# bms_slave.net
KiCad netlist of a schematic drawn in Altium Designer
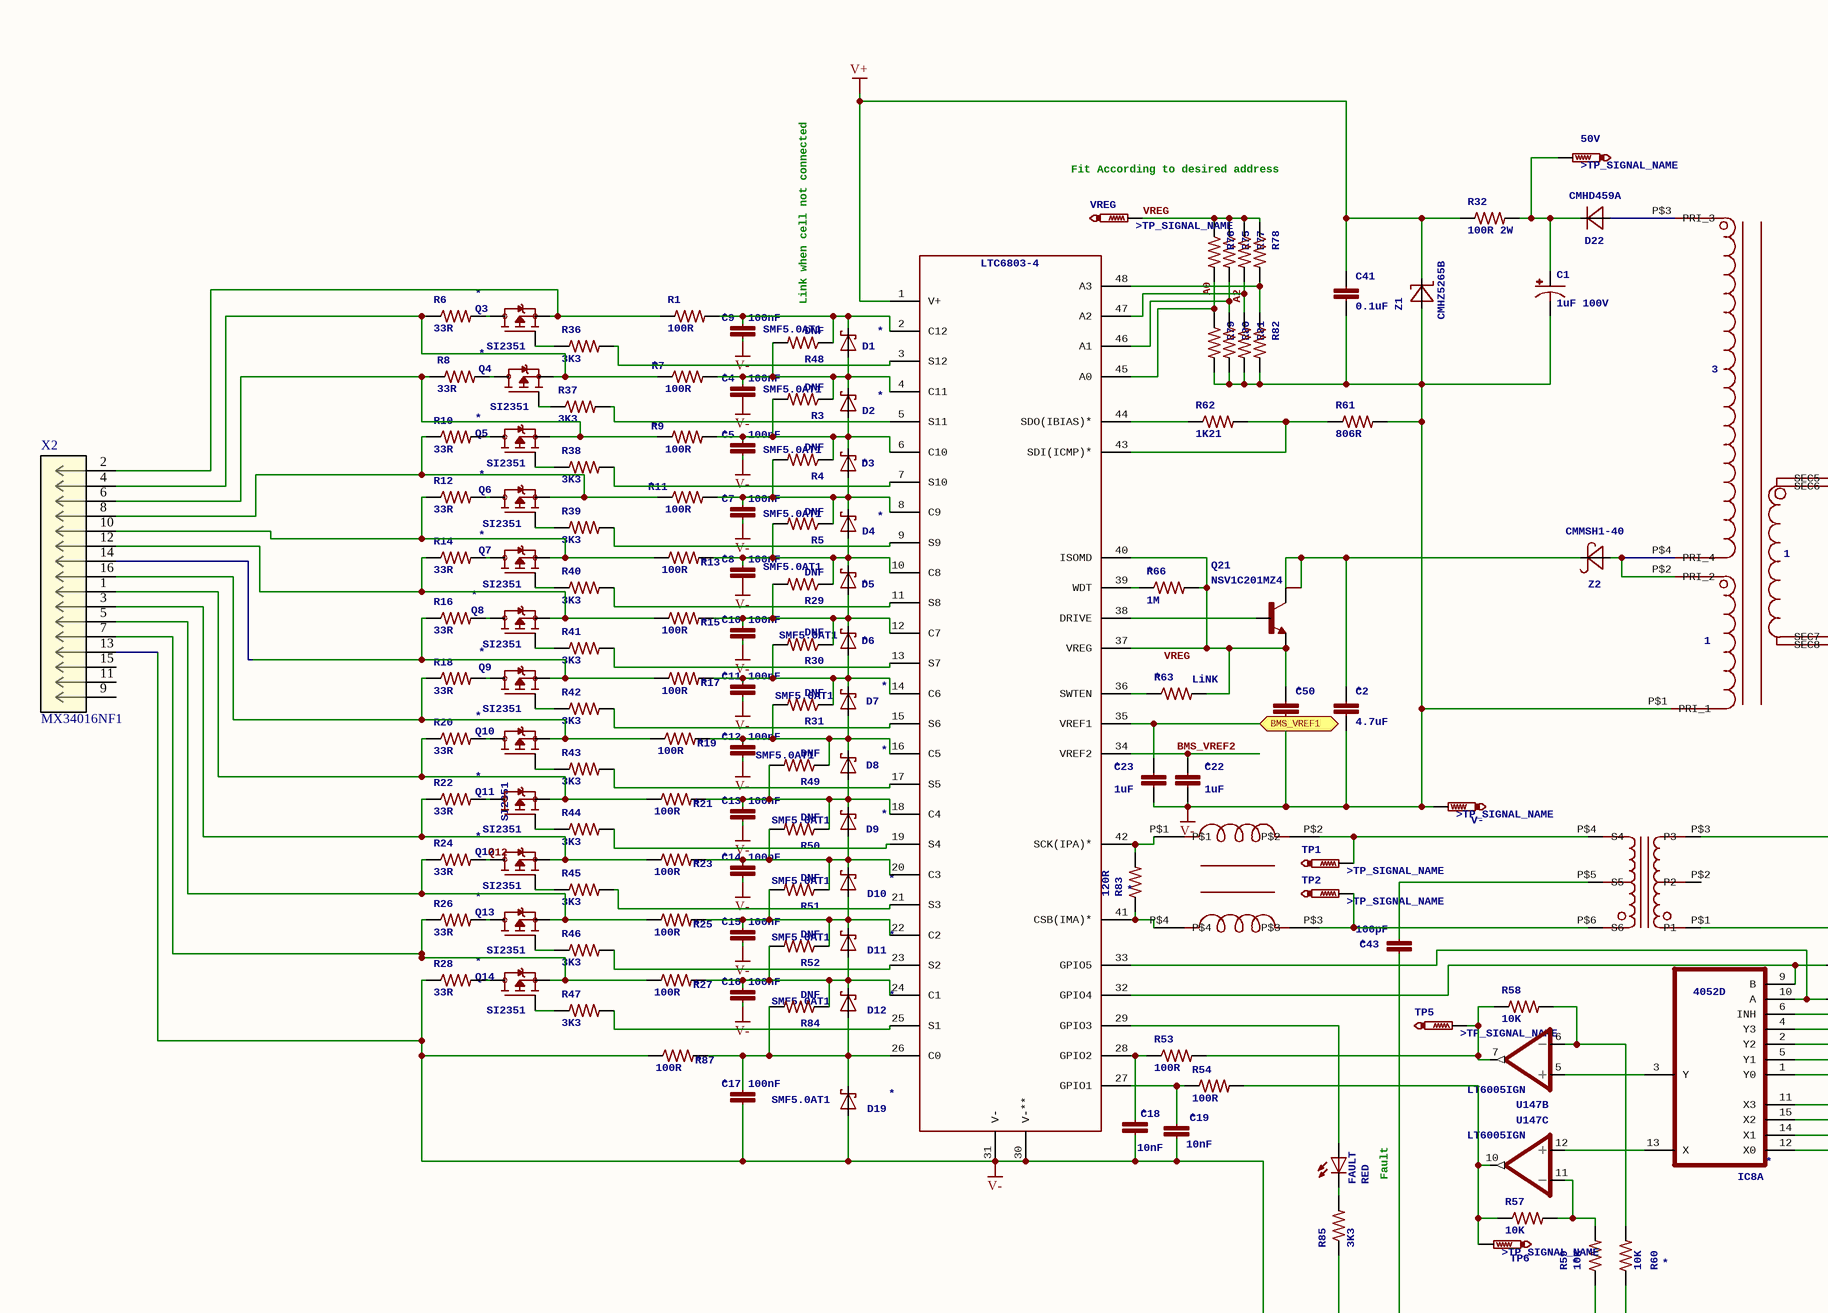
[diagram p0: bms_slave.SchDoc, top left]
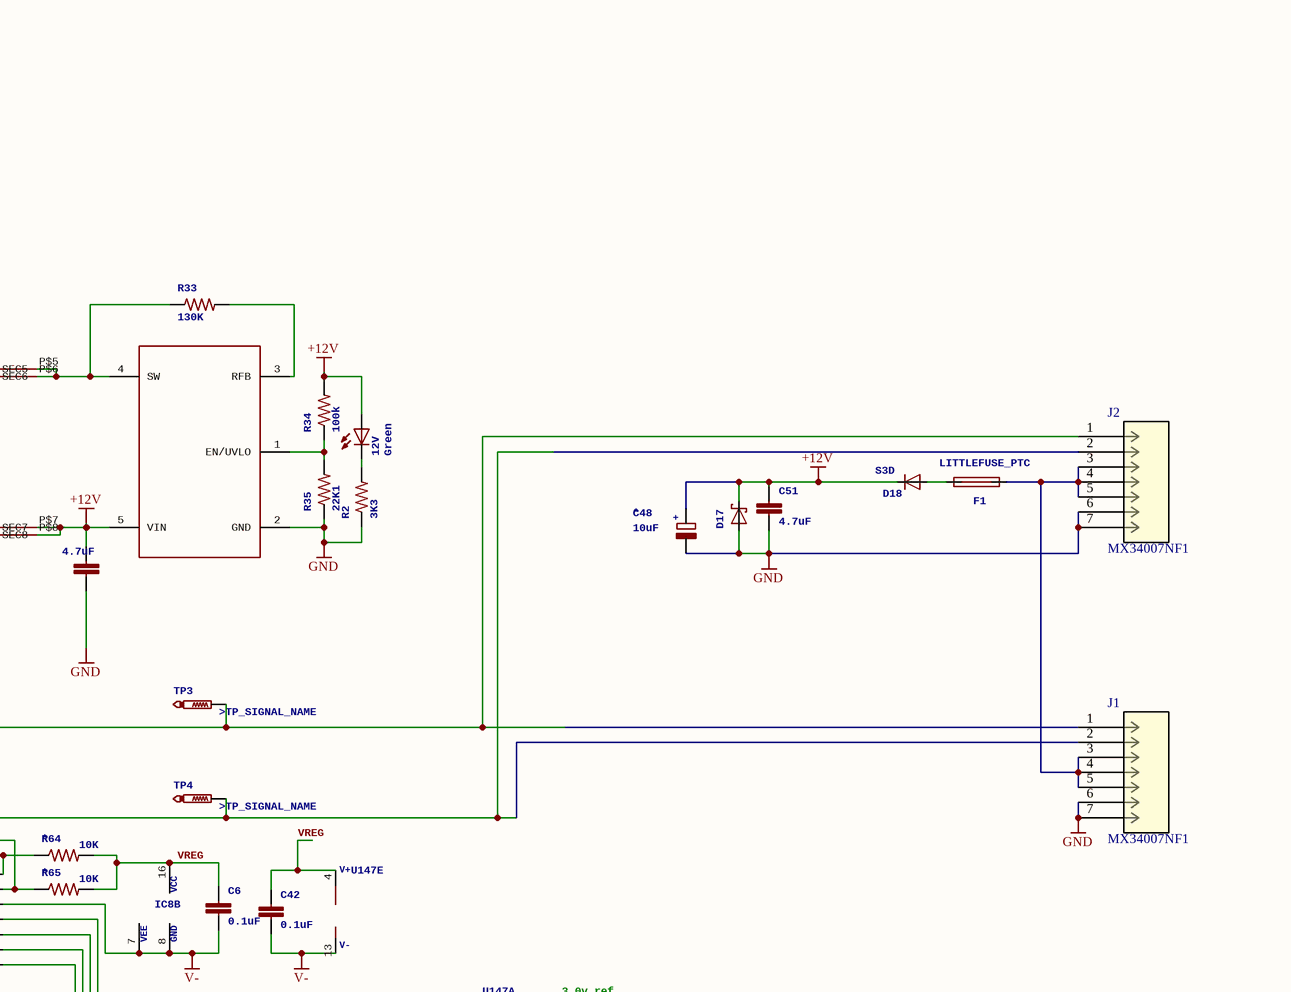
[diagram p1: bms_slave.SchDoc, top right]
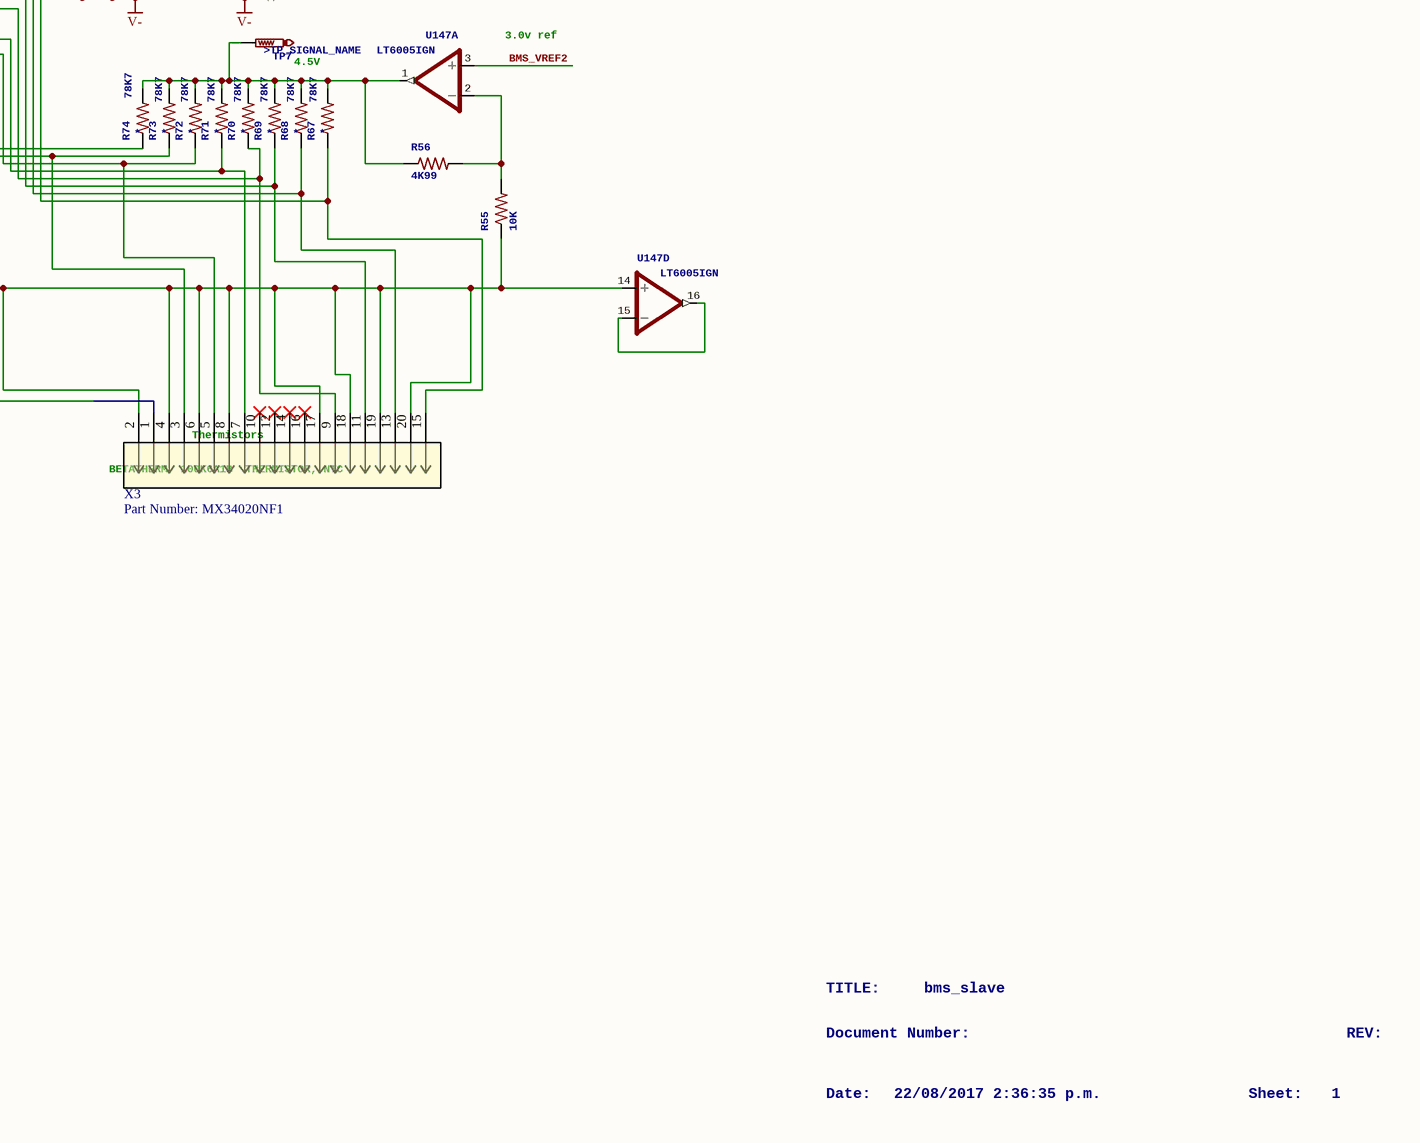
[diagram p2: bms_slave.SchDoc, bottom right]

(export (version "E")
  (design (tool "Eeschema 10.0.6"))
  (components
    (comp (ref "12V")
      (value "Green")
      (footprint "CHIP-LED0805")
      (libsource (lib "led") (part "LEDCHIP-LED0805"))
    )
    (comp (ref "50V")
      (value "PTR1PAD1-13")
      (footprint "P1-13")
      (description "TEST PIN")
      (fields (field (name "TP_SIGNAL_NAME") ">TP_SIGNAL_NAME"))
      (libsource (lib "testpad") (part "PTR1PAD1-13"))
    )
    (comp (ref "C1")
      (value "1uF 100V")
      (footprint "SMC_D")
      (description "POLARIZED CAPACITOR, American symbol")
      (libsource (lib "rcl") (part "CPOL-USSMCD"))
    )
    (comp (ref "C2")
      (value "4.7uF")
      (footprint "C1206")
      (description "CAPACITOR, European symbol")
      (fields (field (name "NAME") "*"))
      (libsource (lib "rcl") (part "C-EUC1206"))
    )
    (comp (ref "C3")
      (value "4.7uF")
      (footprint "C1206")
      (description "CAPACITOR, European symbol")
      (libsource (lib "rcl") (part "C-EUC1206"))
    )
    (comp (ref "C4")
      (value "100nF")
      (footprint "C0603@1")
      (fields (field (name "NAME") "*"))
      (libsource (lib "rcl") (part "C-EU-SMALL_0603"))
    )
    (comp (ref "C5")
      (value "100nF")
      (footprint "C0603@1")
      (fields (field (name "NAME") "*"))
      (libsource (lib "rcl") (part "C-EU-SMALL_0603"))
    )
    (comp (ref "C6")
      (value "0.1uF")
      (footprint "C1206")
      (description "CAPACITOR, European symbol")
      (libsource (lib "rcl") (part "C-EUC1206"))
    )
    (comp (ref "C7")
      (value "100nF")
      (footprint "C0603@1")
      (fields (field (name "NAME") "*"))
      (libsource (lib "rcl") (part "C-EU-SMALL_0603"))
    )
    (comp (ref "C8")
      (value "100nF")
      (footprint "C0603@1")
      (fields (field (name "NAME") "*"))
      (libsource (lib "rcl") (part "C-EU-SMALL_0603"))
    )
    (comp (ref "C9")
      (value "100nF")
      (footprint "C0603@1")
      (fields (field (name "NAME") "*"))
      (libsource (lib "rcl") (part "C-EU-SMALL_0603"))
    )
    (comp (ref "C10")
      (value "100nF")
      (footprint "C0603@1")
      (fields (field (name "NAME") "*"))
      (libsource (lib "rcl") (part "C-EU-SMALL_0603"))
    )
    (comp (ref "C11")
      (value "100nF")
      (footprint "C0603@1")
      (fields (field (name "NAME") "*"))
      (libsource (lib "rcl") (part "C-EU-SMALL_0603"))
    )
    (comp (ref "C12")
      (value "100nF")
      (footprint "C0603@1")
      (fields (field (name "NAME") "*"))
      (libsource (lib "rcl") (part "C-EU-SMALL_0603"))
    )
    (comp (ref "C13")
      (value "100nF")
      (footprint "C0603@1")
      (fields (field (name "NAME") "*"))
      (libsource (lib "rcl") (part "C-EU-SMALL_0603"))
    )
    (comp (ref "C14")
      (value "100nF")
      (footprint "C0603@1")
      (fields (field (name "NAME") "*"))
      (libsource (lib "rcl") (part "C-EU-SMALL_0603"))
    )
    (comp (ref "C15")
      (value "100nF")
      (footprint "C0603@1")
      (fields (field (name "NAME") "*"))
      (libsource (lib "rcl") (part "C-EU-SMALL_0603"))
    )
    (comp (ref "C16")
      (value "100nF")
      (footprint "C0603@1")
      (fields (field (name "NAME") "*"))
      (libsource (lib "rcl") (part "C-EU-SMALL_0603"))
    )
    (comp (ref "C17")
      (value "100nF")
      (footprint "C0603@1")
      (fields (field (name "NAME") "*"))
      (libsource (lib "rcl") (part "C-EU-SMALL_0603"))
    )
    (comp (ref "C18")
      (value "10nF")
      (footprint "C0603@1")
      (fields (field (name "NAME") "*"))
      (libsource (lib "rcl") (part "C-EU-SMALL_0603"))
    )
    (comp (ref "C19")
      (value "10nF")
      (footprint "C0603@1")
      (fields (field (name "NAME") "*"))
      (libsource (lib "rcl") (part "C-EU-SMALL_0603"))
    )
    (comp (ref "C22")
      (value "1uF")
      (footprint "C1206")
      (description "CAPACITOR, European symbol")
      (fields (field (name "NAME") "*"))
      (libsource (lib "rcl") (part "C-EUC1206"))
    )
    (comp (ref "C23")
      (value "1uF")
      (footprint "C1206")
      (description "CAPACITOR, European symbol")
      (fields (field (name "NAME") "*"))
      (libsource (lib "rcl") (part "C-EUC1206"))
    )
    (comp (ref "C41")
      (value "0.1uF")
      (footprint "C1206")
      (description "CAPACITOR, European symbol")
      (libsource (lib "rcl") (part "C-EUC1206"))
    )
    (comp (ref "C42")
      (value "0.1uF")
      (footprint "C1206")
      (description "CAPACITOR, European symbol")
      (libsource (lib "rcl") (part "C-EUC1206"))
    )
    (comp (ref "C43")
      (value "100pF")
      (footprint "C1206@1")
      (fields (field (name "NAME") "*"))
      (libsource (lib "rcl") (part "C-EU-SMALL"))
    )
    (comp (ref "C48")
      (value "10uF")
      (footprint "SMC_D")
      (description "POLARIZED CAPACITOR, European symbol")
      (fields (field (name "NAME") "*") (field (name "+") "+"))
      (libsource (lib "rcl") (part "CPOL-EUSMCD"))
    )
    (comp (ref "C50")
      (value "1uF")
      (footprint "C1206")
      (description "CAPACITOR, European symbol")
      (fields (field (name "NAME") "*"))
      (libsource (lib "rcl") (part "C-EUC1206"))
    )
    (comp (ref "C51")
      (value "4.7uF")
      (footprint "C1206")
      (description "CAPACITOR, European symbol")
      (libsource (lib "rcl") (part "C-EUC1206"))
    )
    (comp (ref "D1")
      (value "SMF5.0AT1")
      (footprint "SOD123FL")
      (description "200 W Transient Voltage Suppressor   Source: Data sheet")
      (fields (field (name "NAME") "*"))
      (libsource (lib "diode") (part "SMF5.0AT1"))
    )
    (comp (ref "D2")
      (value "SMF5.0AT1")
      (footprint "SOD123FL")
      (description "200 W Transient Voltage Suppressor   Source: Data sheet")
      (fields (field (name "NAME") "*"))
      (libsource (lib "diode") (part "SMF5.0AT1"))
    )
    (comp (ref "D3")
      (value "SMF5.0AT1")
      (footprint "SOD123FL")
      (description "200 W Transient Voltage Suppressor   Source: Data sheet")
      (fields (field (name "NAME") "*"))
      (libsource (lib "diode") (part "SMF5.0AT1"))
    )
    (comp (ref "D4")
      (value "SMF5.0AT1")
      (footprint "SOD123FL")
      (description "200 W Transient Voltage Suppressor   Source: Data sheet")
      (fields (field (name "NAME") "*"))
      (libsource (lib "diode") (part "SMF5.0AT1"))
    )
    (comp (ref "D5")
      (value "SMF5.0AT1")
      (footprint "SOD123FL")
      (description "200 W Transient Voltage Suppressor   Source: Data sheet")
      (fields (field (name "NAME") "*"))
      (libsource (lib "diode") (part "SMF5.0AT1"))
    )
    (comp (ref "D6")
      (value "SMF5.0AT1")
      (footprint "SOD123FL")
      (description "200 W Transient Voltage Suppressor   Source: Data sheet")
      (fields (field (name "NAME") "*"))
      (libsource (lib "diode") (part "SMF5.0AT1"))
    )
    (comp (ref "D7")
      (value "SMF5.0AT1")
      (footprint "SOD123FL")
      (description "200 W Transient Voltage Suppressor   Source: Data sheet")
      (fields (field (name "NAME") "*"))
      (libsource (lib "diode") (part "SMF5.0AT1"))
    )
    (comp (ref "D8")
      (value "SMF5.0AT1")
      (footprint "SOD123FL")
      (description "200 W Transient Voltage Suppressor   Source: Data sheet")
      (fields (field (name "NAME") "*"))
      (libsource (lib "diode") (part "SMF5.0AT1"))
    )
    (comp (ref "D9")
      (value "SMF5.0AT1")
      (footprint "SOD123FL")
      (description "200 W Transient Voltage Suppressor   Source: Data sheet")
      (fields (field (name "NAME") "*"))
      (libsource (lib "diode") (part "SMF5.0AT1"))
    )
    (comp (ref "D10")
      (value "SMF5.0AT1")
      (footprint "SOD123FL")
      (description "200 W Transient Voltage Suppressor   Source: Data sheet")
      (fields (field (name "NAME") "*"))
      (libsource (lib "diode") (part "SMF5.0AT1"))
    )
    (comp (ref "D11")
      (value "SMF5.0AT1")
      (footprint "SOD123FL")
      (description "200 W Transient Voltage Suppressor   Source: Data sheet")
      (fields (field (name "NAME") "*"))
      (libsource (lib "diode") (part "SMF5.0AT1"))
    )
    (comp (ref "D12")
      (value "SMF5.0AT1")
      (footprint "SOD123FL")
      (description "200 W Transient Voltage Suppressor   Source: Data sheet")
      (fields (field (name "NAME") "*"))
      (libsource (lib "diode") (part "SMF5.0AT1"))
    )
    (comp (ref "D17")
      (value "SCHOTTKY-DIODESMC")
      (footprint "SMC")
      (description "Schottky Diode")
      (libsource (lib "diode") (part "SCHOTTKY-DIODESMC"))
    )
    (comp (ref "D18")
      (value "S3D")
      (footprint "SMC")
      (description "DIODE")
      (libsource (lib "diode") (part "DIODE-SMC"))
    )
    (comp (ref "D19")
      (value "SMF5.0AT1")
      (footprint "SOD123FL")
      (description "200 W Transient Voltage Suppressor   Source: Data sheet")
      (fields (field (name "NAME") "*"))
      (libsource (lib "diode") (part "SMF5.0AT1"))
    )
    (comp (ref "D22") (value "CMHD459A") (footprint "SOD123") (libsource (lib "diode") (part "CMHD459A")))
    (comp (ref "F1")
      (value "LITTLEFUSE_PTC")
      (footprint "1812")
      (libsource (lib "fuse") (part "LITTLEFUSE_PTC"))
    )
    (comp (ref "FAULT")
      (value "RED")
      (footprint "CHIP-LED0805")
      (libsource (lib "led") (part "LEDCHIP-LED0805"))
    )
    (comp (ref "IC8")
      (value "4052D")
      (footprint "SO16")
      (description "Dual 4-channel ANALOG MULTIPLEXER")
      (fields
        (field (name "NAME") "*")
        (field (name "VEE") "VEE")
        (field (name "GND") "GND")
        (field (name "VCC") "VCC")
      )
      (libsource (lib "40xx") (part "4052D"))
    )
    (comp (ref "J1")
      (value "MX34007NF1")
      (footprint "CONN_MX34007NF1")
      (libsource (lib "2020-03-25_00-51-49") (part "MX34007NF1"))
    )
    (comp (ref "J2")
      (value "MX34007NF1")
      (footprint "CONN_MX34007NF1")
      (libsource (lib "2020-03-25_00-51-49") (part "MX34007NF1"))
    )
    (comp (ref "Q3")
      (value "SI2351")
      (footprint "SOT23")
      (fields (field (name "NAME") "*"))
      (libsource (lib "transistor-fet") (part "SI2351"))
    )
    (comp (ref "Q4")
      (value "SI2351")
      (footprint "SOT23")
      (fields (field (name "NAME") "*"))
      (libsource (lib "transistor-fet") (part "SI2351"))
    )
    (comp (ref "Q5")
      (value "SI2351")
      (footprint "SOT23")
      (fields (field (name "NAME") "*"))
      (libsource (lib "transistor-fet") (part "SI2351"))
    )
    (comp (ref "Q6")
      (value "SI2351")
      (footprint "SOT23")
      (fields (field (name "NAME") "*"))
      (libsource (lib "transistor-fet") (part "SI2351"))
    )
    (comp (ref "Q7")
      (value "SI2351")
      (footprint "SOT23")
      (fields (field (name "NAME") "*"))
      (libsource (lib "transistor-fet") (part "SI2351"))
    )
    (comp (ref "Q8")
      (value "SI2351")
      (footprint "SOT23")
      (fields (field (name "NAME") "*"))
      (libsource (lib "transistor-fet") (part "SI2351"))
    )
    (comp (ref "Q9")
      (value "SI2351")
      (footprint "SOT23")
      (fields (field (name "NAME") "*"))
      (libsource (lib "transistor-fet") (part "SI2351"))
    )
    (comp (ref "Q10")
      (value "SI2351")
      (footprint "SOT23")
      (fields (field (name "NAME") "*"))
      (libsource (lib "transistor-fet") (part "SI2351"))
    )
    (comp (ref "Q11")
      (value "SI2351")
      (footprint "SOT23")
      (fields (field (name "NAME") "*"))
      (libsource (lib "transistor-fet") (part "SI2351"))
    )
    (comp (ref "Q12")
      (value "SI2351")
      (footprint "SOT23")
      (fields (field (name "NAME") "*"))
      (libsource (lib "transistor-fet") (part "SI2351"))
    )
    (comp (ref "Q13")
      (value "SI2351")
      (footprint "SOT23")
      (fields (field (name "NAME") "*"))
      (libsource (lib "transistor-fet") (part "SI2351"))
    )
    (comp (ref "Q14")
      (value "SI2351")
      (footprint "SOT23")
      (fields (field (name "NAME") "*"))
      (libsource (lib "transistor-fet") (part "SI2351"))
    )
    (comp (ref "Q21")
      (value "NSV1C201MZ4")
      (footprint "SOT223")
      (libsource (lib "transistor-npn") (part "NSV1C201MZ4"))
    )
    (comp (ref "R1")
      (value "100R")
      (footprint "R0603")
      (description "RESISTOR, American symbol")
      (libsource (lib "rcl") (part "R-US_R0603"))
    )
    (comp (ref "R2")
      (value "3K3")
      (footprint "R0603")
      (description "RESISTOR, American symbol")
      (libsource (lib "rcl") (part "R-US_R0603"))
    )
    (comp (ref "R3")
      (value "DNF")
      (footprint "R0603")
      (description "RESISTOR, American symbol")
      (libsource (lib "rcl") (part "R-US_R0603"))
    )
    (comp (ref "R4")
      (value "DNF")
      (footprint "R0603")
      (description "RESISTOR, American symbol")
      (libsource (lib "rcl") (part "R-US_R0603"))
    )
    (comp (ref "R5")
      (value "DNF")
      (footprint "R0603")
      (description "RESISTOR, American symbol")
      (libsource (lib "rcl") (part "R-US_R0603"))
    )
    (comp (ref "R6")
      (value "33R")
      (footprint "R2512")
      (description "RESISTOR, American symbol")
      (libsource (lib "rcl") (part "R-US_R2512"))
    )
    (comp (ref "R7")
      (value "100R")
      (footprint "R0603")
      (description "RESISTOR, American symbol")
      (fields (field (name "NAME") "*"))
      (libsource (lib "rcl") (part "R-US_R0603"))
    )
    (comp (ref "R8")
      (value "33R")
      (footprint "R2512")
      (description "RESISTOR, American symbol")
      (libsource (lib "rcl") (part "R-US_R2512"))
    )
    (comp (ref "R9")
      (value "100R")
      (footprint "R0603")
      (description "RESISTOR, American symbol")
      (fields (field (name "NAME") "*"))
      (libsource (lib "rcl") (part "R-US_R0603"))
    )
    (comp (ref "R10")
      (value "33R")
      (footprint "R2512")
      (description "RESISTOR, American symbol")
      (libsource (lib "rcl") (part "R-US_R2512"))
    )
    (comp (ref "R11")
      (value "100R")
      (footprint "R0603")
      (description "RESISTOR, American symbol")
      (fields (field (name "NAME") "*"))
      (libsource (lib "rcl") (part "R-US_R0603"))
    )
    (comp (ref "R12")
      (value "33R")
      (footprint "R2512")
      (description "RESISTOR, American symbol")
      (libsource (lib "rcl") (part "R-US_R2512"))
    )
    (comp (ref "R13")
      (value "100R")
      (footprint "R0603")
      (description "RESISTOR, American symbol")
      (fields (field (name "NAME") "*"))
      (libsource (lib "rcl") (part "R-US_R0603"))
    )
    (comp (ref "R14")
      (value "33R")
      (footprint "R2512")
      (description "RESISTOR, American symbol")
      (libsource (lib "rcl") (part "R-US_R2512"))
    )
    (comp (ref "R15")
      (value "100R")
      (footprint "R0603")
      (description "RESISTOR, American symbol")
      (fields (field (name "NAME") "*"))
      (libsource (lib "rcl") (part "R-US_R0603"))
    )
    (comp (ref "R16")
      (value "33R")
      (footprint "R2512")
      (description "RESISTOR, American symbol")
      (libsource (lib "rcl") (part "R-US_R2512"))
    )
    (comp (ref "R17")
      (value "100R")
      (footprint "R0603")
      (description "RESISTOR, American symbol")
      (fields (field (name "NAME") "*"))
      (libsource (lib "rcl") (part "R-US_R0603"))
    )
    (comp (ref "R18")
      (value "33R")
      (footprint "R2512")
      (description "RESISTOR, American symbol")
      (libsource (lib "rcl") (part "R-US_R2512"))
    )
    (comp (ref "R19")
      (value "100R")
      (footprint "R0603")
      (description "RESISTOR, American symbol")
      (fields (field (name "NAME") "*"))
      (libsource (lib "rcl") (part "R-US_R0603"))
    )
    (comp (ref "R20")
      (value "33R")
      (footprint "R2512")
      (description "RESISTOR, American symbol")
      (libsource (lib "rcl") (part "R-US_R2512"))
    )
    (comp (ref "R21")
      (value "100R")
      (footprint "R0603")
      (description "RESISTOR, American symbol")
      (fields (field (name "NAME") "*"))
      (libsource (lib "rcl") (part "R-US_R0603"))
    )
    (comp (ref "R22")
      (value "33R")
      (footprint "R2512")
      (description "RESISTOR, American symbol")
      (libsource (lib "rcl") (part "R-US_R2512"))
    )
    (comp (ref "R23")
      (value "100R")
      (footprint "R0603")
      (description "RESISTOR, American symbol")
      (fields (field (name "NAME") "*"))
      (libsource (lib "rcl") (part "R-US_R0603"))
    )
    (comp (ref "R24")
      (value "33R")
      (footprint "R2512")
      (description "RESISTOR, American symbol")
      (libsource (lib "rcl") (part "R-US_R2512"))
    )
    (comp (ref "R25")
      (value "100R")
      (footprint "R0603")
      (description "RESISTOR, American symbol")
      (fields (field (name "NAME") "*"))
      (libsource (lib "rcl") (part "R-US_R0603"))
    )
    (comp (ref "R26")
      (value "33R")
      (footprint "R2512")
      (description "RESISTOR, American symbol")
      (libsource (lib "rcl") (part "R-US_R2512"))
    )
    (comp (ref "R27")
      (value "100R")
      (footprint "R0603")
      (description "RESISTOR, American symbol")
      (fields (field (name "NAME") "*"))
      (libsource (lib "rcl") (part "R-US_R0603"))
    )
    (comp (ref "R28")
      (value "33R")
      (footprint "R2512")
      (description "RESISTOR, American symbol")
      (libsource (lib "rcl") (part "R-US_R2512"))
    )
    (comp (ref "R29")
      (value "DNF")
      (footprint "R0603")
      (description "RESISTOR, American symbol")
      (libsource (lib "rcl") (part "R-US_R0603"))
    )
    (comp (ref "R30")
      (value "DNF")
      (footprint "R0603")
      (description "RESISTOR, American symbol")
      (libsource (lib "rcl") (part "R-US_R0603"))
    )
    (comp (ref "R31")
      (value "DNF")
      (footprint "R0603")
      (description "RESISTOR, American symbol")
      (libsource (lib "rcl") (part "R-US_R0603"))
    )
    (comp (ref "R32")
      (value "100R 2W")
      (footprint "R2512")
      (description "RESISTOR, American symbol")
      (libsource (lib "rcl") (part "R-US_R2512"))
    )
    (comp (ref "R33")
      (value "130K")
      (footprint "R0603")
      (description "RESISTOR, American symbol")
      (libsource (lib "rcl") (part "R-US_R0603"))
    )
    (comp (ref "R34")
      (value "100k")
      (footprint "R0603")
      (description "RESISTOR, American symbol")
      (libsource (lib "rcl") (part "R-US_R0603"))
    )
    (comp (ref "R35")
      (value "22K1")
      (footprint "R0603")
      (description "RESISTOR, American symbol")
      (libsource (lib "rcl") (part "R-US_R0603"))
    )
    (comp (ref "R36")
      (value "3K3")
      (footprint "R0603")
      (description "RESISTOR, American symbol")
      (libsource (lib "rcl") (part "R-US_R0603"))
    )
    (comp (ref "R37")
      (value "3K3")
      (footprint "R0603")
      (description "RESISTOR, American symbol")
      (libsource (lib "rcl") (part "R-US_R0603"))
    )
    (comp (ref "R38")
      (value "3K3")
      (footprint "R0603")
      (description "RESISTOR, American symbol")
      (libsource (lib "rcl") (part "R-US_R0603"))
    )
    (comp (ref "R39")
      (value "3K3")
      (footprint "R0603")
      (description "RESISTOR, American symbol")
      (libsource (lib "rcl") (part "R-US_R0603"))
    )
    (comp (ref "R40")
      (value "3K3")
      (footprint "R0603")
      (description "RESISTOR, American symbol")
      (libsource (lib "rcl") (part "R-US_R0603"))
    )
    (comp (ref "R41")
      (value "3K3")
      (footprint "R0603")
      (description "RESISTOR, American symbol")
      (libsource (lib "rcl") (part "R-US_R0603"))
    )
    (comp (ref "R42")
      (value "3K3")
      (footprint "R0603")
      (description "RESISTOR, American symbol")
      (libsource (lib "rcl") (part "R-US_R0603"))
    )
    (comp (ref "R43")
      (value "3K3")
      (footprint "R0603")
      (description "RESISTOR, American symbol")
      (libsource (lib "rcl") (part "R-US_R0603"))
    )
    (comp (ref "R44")
      (value "3K3")
      (footprint "R0603")
      (description "RESISTOR, American symbol")
      (libsource (lib "rcl") (part "R-US_R0603"))
    )
    (comp (ref "R45")
      (value "3K3")
      (footprint "R0603")
      (description "RESISTOR, American symbol")
      (libsource (lib "rcl") (part "R-US_R0603"))
    )
    (comp (ref "R46")
      (value "3K3")
      (footprint "R0603")
      (description "RESISTOR, American symbol")
      (libsource (lib "rcl") (part "R-US_R0603"))
    )
    (comp (ref "R47")
      (value "3K3")
      (footprint "R0603")
      (description "RESISTOR, American symbol")
      (libsource (lib "rcl") (part "R-US_R0603"))
    )
    (comp (ref "R48")
      (value "DNF")
      (footprint "R0603")
      (description "RESISTOR, American symbol")
      (libsource (lib "rcl") (part "R-US_R0603"))
    )
    (comp (ref "R49")
      (value "DNF")
      (footprint "R0603")
      (description "RESISTOR, American symbol")
      (libsource (lib "rcl") (part "R-US_R0603"))
    )
    (comp (ref "R50")
      (value "DNF")
      (footprint "R0603")
      (description "RESISTOR, American symbol")
      (libsource (lib "rcl") (part "R-US_R0603"))
    )
    (comp (ref "R51")
      (value "DNF")
      (footprint "R0603")
      (description "RESISTOR, American symbol")
      (libsource (lib "rcl") (part "R-US_R0603"))
    )
    (comp (ref "R52")
      (value "DNF")
      (footprint "R0603")
      (description "RESISTOR, American symbol")
      (libsource (lib "rcl") (part "R-US_R0603"))
    )
    (comp (ref "R53")
      (value "100R")
      (footprint "R0603")
      (description "RESISTOR, American symbol")
      (libsource (lib "rcl") (part "R-US_R0603"))
    )
    (comp (ref "R54")
      (value "100R")
      (footprint "R0603")
      (description "RESISTOR, American symbol")
      (libsource (lib "rcl") (part "R-US_R0603"))
    )
    (comp (ref "R55")
      (value "10K")
      (footprint "R0603")
      (description "RESISTOR, American symbol")
      (libsource (lib "rcl") (part "R-US_R0603"))
    )
    (comp (ref "R56")
      (value "4K99")
      (footprint "R0603")
      (description "RESISTOR, American symbol")
      (libsource (lib "rcl") (part "R-US_R0603"))
    )
    (comp (ref "R57")
      (value "10K")
      (footprint "R0603")
      (description "RESISTOR, American symbol")
      (libsource (lib "rcl") (part "R-US_R0603"))
    )
    (comp (ref "R58")
      (value "10K")
      (footprint "R0603")
      (description "RESISTOR, American symbol")
      (libsource (lib "rcl") (part "R-US_R0603"))
    )
    (comp (ref "R59")
      (value "10K")
      (footprint "R0603")
      (description "RESISTOR, American symbol")
      (fields (field (name "NAME") "*"))
      (libsource (lib "rcl") (part "R-US_R0603"))
    )
    (comp (ref "R60")
      (value "10K")
      (footprint "R0603")
      (description "RESISTOR, American symbol")
      (fields (field (name "NAME") "*"))
      (libsource (lib "rcl") (part "R-US_R0603"))
    )
    (comp (ref "R61")
      (value "806R")
      (footprint "R0603")
      (description "RESISTOR, American symbol")
      (libsource (lib "rcl") (part "R-US_R0603"))
    )
    (comp (ref "R62")
      (value "1K21")
      (footprint "R0603")
      (description "RESISTOR, American symbol")
      (libsource (lib "rcl") (part "R-US_R0603"))
    )
    (comp (ref "R63")
      (value "LiNK")
      (footprint "R0603")
      (description "RESISTOR, American symbol")
      (fields (field (name "NAME") "*"))
      (libsource (lib "rcl") (part "R-US_R0603"))
    )
    (comp (ref "R64")
      (value "10K")
      (footprint "R0603")
      (description "RESISTOR, American symbol")
      (fields (field (name "NAME") "*"))
      (libsource (lib "rcl") (part "R-US_R0603"))
    )
    (comp (ref "R65")
      (value "10K")
      (footprint "R0603")
      (description "RESISTOR, American symbol")
      (fields (field (name "NAME") "*"))
      (libsource (lib "rcl") (part "R-US_R0603"))
    )
    (comp (ref "R66")
      (value "1M")
      (footprint "R0603")
      (description "RESISTOR, American symbol")
      (fields (field (name "NAME") "*"))
      (libsource (lib "rcl") (part "R-US_R0603"))
    )
    (comp (ref "R67")
      (value "78K7")
      (footprint "R0603")
      (description "RESISTOR, American symbol")
      (fields (field (name "NAME") "*"))
      (libsource (lib "rcl") (part "R-US_R0603"))
    )
    (comp (ref "R68")
      (value "78K7")
      (footprint "R0603")
      (description "RESISTOR, American symbol")
      (fields (field (name "NAME") "*"))
      (libsource (lib "rcl") (part "R-US_R0603"))
    )
    (comp (ref "R69")
      (value "78K7")
      (footprint "R0603")
      (description "RESISTOR, American symbol")
      (fields (field (name "NAME") "*"))
      (libsource (lib "rcl") (part "R-US_R0603"))
    )
    (comp (ref "R70")
      (value "78K7")
      (footprint "R0603")
      (description "RESISTOR, American symbol")
      (fields (field (name "NAME") "*"))
      (libsource (lib "rcl") (part "R-US_R0603"))
    )
    (comp (ref "R71")
      (value "78K7")
      (footprint "R0603")
      (description "RESISTOR, American symbol")
      (fields (field (name "NAME") "*"))
      (libsource (lib "rcl") (part "R-US_R0603"))
    )
    (comp (ref "R72")
      (value "78K7")
      (footprint "R0603")
      (description "RESISTOR, American symbol")
      (fields (field (name "NAME") "*"))
      (libsource (lib "rcl") (part "R-US_R0603"))
    )
    (comp (ref "R73")
      (value "78K7")
      (footprint "R0603")
      (description "RESISTOR, American symbol")
      (fields (field (name "NAME") "*"))
      (libsource (lib "rcl") (part "R-US_R0603"))
    )
    (comp (ref "R74")
      (value "78K7")
      (footprint "R0603")
      (description "RESISTOR, American symbol")
      (fields (field (name "NAME") "*"))
      (libsource (lib "rcl") (part "R-US_R0603"))
    )
    (comp (ref "R75")
      (value "R-US_R0603")
      (footprint "R0603")
      (description "RESISTOR, American symbol")
      (libsource (lib "rcl") (part "R-US_R0603"))
    )
    (comp (ref "R76")
      (value "R-US_R0603")
      (footprint "R0603")
      (description "RESISTOR, American symbol")
      (libsource (lib "rcl") (part "R-US_R0603"))
    )
    (comp (ref "R77")
      (value "R-US_R0603")
      (footprint "R0603")
      (description "RESISTOR, American symbol")
      (libsource (lib "rcl") (part "R-US_R0603"))
    )
    (comp (ref "R78")
      (value "R-US_R0603")
      (footprint "R0603")
      (description "RESISTOR, American symbol")
      (libsource (lib "rcl") (part "R-US_R0603"))
    )
    (comp (ref "R79")
      (value "R-US_R0603")
      (footprint "R0603")
      (description "RESISTOR, American symbol")
      (libsource (lib "rcl") (part "R-US_R0603"))
    )
    (comp (ref "R80")
      (value "R-US_R0603")
      (footprint "R0603")
      (description "RESISTOR, American symbol")
      (libsource (lib "rcl") (part "R-US_R0603"))
    )
    (comp (ref "R81")
      (value "R-US_R0603")
      (footprint "R0603")
      (description "RESISTOR, American symbol")
      (libsource (lib "rcl") (part "R-US_R0603"))
    )
    (comp (ref "R82")
      (value "R-US_R0603")
      (footprint "R0603")
      (description "RESISTOR, American symbol")
      (libsource (lib "rcl") (part "R-US_R0603"))
    )
    (comp (ref "R83")
      (value "120R")
      (footprint "R0603")
      (description "RESISTOR, American symbol")
      (fields (field (name "NAME") "*"))
      (libsource (lib "rcl") (part "R-US_R0603"))
    )
    (comp (ref "R84")
      (value "DNF")
      (footprint "R0603")
      (description "RESISTOR, American symbol")
      (libsource (lib "rcl") (part "R-US_R0603"))
    )
    (comp (ref "R85")
      (value "3K3")
      (footprint "R0603")
      (description "RESISTOR, American symbol")
      (libsource (lib "rcl") (part "R-US_R0603"))
    )
    (comp (ref "R87")
      (value "100R")
      (footprint "R0603")
      (description "RESISTOR, American symbol")
      (fields (field (name "NAME") "*"))
      (libsource (lib "rcl") (part "R-US_R0603"))
    )
    (comp (ref "TP1")
      (value "PTR1PAD1-13")
      (footprint "P1-13")
      (description "TEST PIN")
      (fields (field (name "TP_SIGNAL_NAME") ">TP_SIGNAL_NAME"))
      (libsource (lib "") (part "PTR1PAD1-13_1"))
    )
    (comp (ref "TP2")
      (value "PTR1PAD1-13")
      (footprint "P1-13")
      (description "TEST PIN")
      (fields (field (name "TP_SIGNAL_NAME") ">TP_SIGNAL_NAME"))
      (libsource (lib "") (part "PTR1PAD1-13_1"))
    )
    (comp (ref "TP3")
      (value "PTR1PAD1-13")
      (footprint "P1-13")
      (description "TEST PIN")
      (fields (field (name "TP_SIGNAL_NAME") ">TP_SIGNAL_NAME"))
      (libsource (lib "") (part "PTR1PAD1-13_1"))
    )
    (comp (ref "TP4")
      (value "PTR1PAD1-13")
      (footprint "P1-13")
      (description "TEST PIN")
      (fields (field (name "TP_SIGNAL_NAME") ">TP_SIGNAL_NAME"))
      (libsource (lib "") (part "PTR1PAD1-13_1"))
    )
    (comp (ref "TP5")
      (value "PTR1PAD1-13")
      (footprint "P1-13")
      (description "TEST PIN")
      (fields (field (name "TP_SIGNAL_NAME") ">TP_SIGNAL_NAME"))
      (libsource (lib "") (part "PTR1PAD1-13_1"))
    )
    (comp (ref "TP6")
      (value "PTR1PAD1-13")
      (footprint "P1-13")
      (description "TEST PIN")
      (fields (field (name "TP_SIGNAL_NAME") ">TP_SIGNAL_NAME"))
      (libsource (lib "testpad") (part "PTR1PAD1-13"))
    )
    (comp (ref "TP7")
      (value "PTR1PAD1-13")
      (footprint "P1-13")
      (description "TEST PIN")
      (fields (field (name "TP_SIGNAL_NAME") ">TP_SIGNAL_NAME"))
      (libsource (lib "testpad") (part "PTR1PAD1-13"))
    )
    (comp (ref "U$1")
      (value "DLW43SH510XK2")
      (footprint "DLW43S")
      (libsource (lib "murata-filter") (part "DLW43SH510XK2"))
    )
    (comp (ref "U$3") (value "T3001NL") (footprint "T3001NL") (libsource (lib "pulse-eng") (part "T3001NL")))
    (comp (ref "U$15")
      (value "WURTH_750370040")
      (footprint "WE_750370040")
      (fields (field (name "1") "1") (field (name "1_1") "1") (field (name "3") "3"))
      (libsource (lib "bms_slave") (part "WURTH_750370040"))
    )
    (comp (ref "U1")
      (value "LTC6804-2")
      (footprint "SSOP48")
      (fields (field (name "LTC6803-4") "LTC6803-4"))
      (libsource (lib "linear-technology") (part "LTC6804-2"))
    )
    (comp (ref "U21")
      (value "LT8300")
      (footprint "TSOT23-5")
      (libsource (lib "linear-technology") (part "LT8300"))
    )
    (comp (ref "U147")
      (value "LT6005IGN")
      (footprint "TSSOP16")
      (fields (field (name "V+") "V+") (field (name "V-") "V-"))
      (libsource (lib "linear-technology") (part "LT6005IGN"))
    )
    (comp (ref "V-")
      (value "PTR1PAD1-13")
      (footprint "P1-13")
      (description "TEST PIN")
      (fields (field (name "TP_SIGNAL_NAME") ">TP_SIGNAL_NAME"))
      (libsource (lib "testpad") (part "PTR1PAD1-13"))
    )
    (comp (ref "VREG")
      (value "PTR1PAD1-13")
      (footprint "P1-13")
      (description "TEST PIN")
      (fields (field (name "TP_SIGNAL_NAME") ">TP_SIGNAL_NAME"))
      (libsource (lib "") (part "PTR1PAD1-13_1"))
    )
    (comp (ref "X2") (value "MX34016NF1") (libsource (lib "2020-04-26_00-24-06") (part "MX34016NF1")))
    (comp (ref "X3")
      (value "Part Number: MX34020NF1")
      (description "No Description Available")
      (fields
        (field (name "MANUFACTURER_PART_NUMBER") "MX34020NF1")
        (field (name "COPYRIGHT") "Copyright (C) 2018 Accelerated Designs. All rights reserved")
      )
      (libsource (lib "2020-04-26_00-24-06") (part "MX34020NF1"))
    )
    (comp (ref "Z1") (value "CMHZ5265B") (footprint "SOD123") (libsource (lib "diode") (part "CMHZ5265B")))
    (comp (ref "Z2") (value "CMMSH1-40") (footprint "SOD123") (libsource (lib "diode") (part "CMMSH1-40")))
  )
  (nets
    (net (code "1") (name "+12V") (class "Default")
      (node (ref "12V") (pin "A") (pinfunction "A_A") (pintype "passive"))
      (node (ref "C3") (pin "1") (pinfunction "1_1") (pintype "passive"))
      (node (ref "C48") (pin "+") (pinfunction "+_+") (pintype "passive"))
      (node (ref "C51") (pin "1") (pinfunction "1_1") (pintype "passive"))
      (node (ref "D17") (pin "C") (pinfunction "C_C") (pintype "passive"))
      (node (ref "D18") (pin "C") (pinfunction "C_C") (pintype "passive"))
      (node (ref "R34") (pin "2") (pinfunction "2_2") (pintype "passive"))
      (node (ref "U$15") (pin "P$7") (pinfunction "SEC7_P$7") (pintype "passive"))
      (node (ref "U$15") (pin "P$8") (pinfunction "SEC8_P$8") (pintype "passive"))
      (node (ref "U21") (pin "5") (pinfunction "VIN_5") (pintype "passive"))
    )
    (net (code "2") (name "/A0") (class "Default")
      (node (ref "R76") (pin "2") (pinfunction "2_2") (pintype "passive"))
      (node (ref "R79") (pin "1") (pinfunction "1_1") (pintype "passive"))
      (node (ref "U1") (pin "45") (pinfunction "A0_45") (pintype "passive"))
    )
    (net (code "3") (name "/A2") (class "Default")
      (node (ref "R77") (pin "2") (pinfunction "2_2") (pintype "passive"))
      (node (ref "R81") (pin "1") (pinfunction "1_1") (pintype "passive"))
      (node (ref "U1") (pin "47") (pinfunction "A2_47") (pintype "passive"))
    )
    (net (code "4") (name "/BMS_VREF1") (class "Default")
      (node (ref "C23") (pin "1") (pinfunction "1_1") (pintype "passive"))
      (node (ref "U1") (pin "35") (pinfunction "VREF1_35") (pintype "passive"))
    )
    (net (code "5") (name "/BMS_VREF2") (class "Default")
      (node (ref "C22") (pin "1") (pinfunction "1_1") (pintype "passive"))
      (node (ref "U1") (pin "34") (pinfunction "VREF2_34") (pintype "passive"))
      (node (ref "U147") (pin "3") (pinfunction "+IN_3") (pintype "passive"))
    )
    (net (code "6") (name "/Q12") (class "Default")
      (node (ref "Q12") (pin "3") (pinfunction "D_3") (pintype "passive"))
      (node (ref "R24") (pin "2") (pinfunction "2_2") (pintype "passive"))
    )
    (net (code "7") (name "/VREG") (class "Default")
      (node (ref "C42") (pin "1") (pinfunction "1_1") (pintype "passive"))
      (node (ref "C50") (pin "1") (pinfunction "1_1") (pintype "passive"))
      (node (ref "C6") (pin "1") (pinfunction "1_1") (pintype "passive"))
      (node (ref "IC8") (pin "16") (pinfunction "VCC_16") (pintype "power_in"))
      (node (ref "Q21") (pin "3") (pinfunction "E_3") (pintype "passive"))
      (node (ref "R63") (pin "2") (pinfunction "2_2") (pintype "passive"))
      (node (ref "R64") (pin "2") (pinfunction "2_2") (pintype "passive"))
      (node (ref "R65") (pin "2") (pinfunction "2_2") (pintype "passive"))
      (node (ref "R66") (pin "2") (pinfunction "2_2") (pintype "passive"))
      (node (ref "R75") (pin "1") (pinfunction "1_1") (pintype "passive"))
      (node (ref "R76") (pin "1") (pinfunction "1_1") (pintype "passive"))
      (node (ref "R77") (pin "1") (pinfunction "1_1") (pintype "passive"))
      (node (ref "R78") (pin "1") (pinfunction "1_1") (pintype "passive"))
      (node (ref "U1") (pin "37") (pinfunction "VREG_37") (pintype "power_in"))
      (node (ref "U1") (pin "40") (pinfunction "ISOMD_40") (pintype "passive"))
      (node (ref "U147") (pin "4") (pinfunction "V+_4") (pintype "power_in"))
      (node (ref "VREG") (pin "TP") (pinfunction "TP_TP") (pintype "passive"))
    )
    (net (code "8") (name "GND") (class "Default")
      (node (ref "C3") (pin "2") (pinfunction "2_2") (pintype "passive"))
      (node (ref "C48") (pin "-") (pinfunction "-_-") (pintype "passive"))
      (node (ref "C51") (pin "2") (pinfunction "2_2") (pintype "passive"))
      (node (ref "D17") (pin "A") (pinfunction "A_A") (pintype "passive"))
      (node (ref "J1") (pin "6") (pinfunction "6_6") (pintype "passive"))
      (node (ref "J1") (pin "7") (pinfunction "7_7") (pintype "passive"))
      (node (ref "J2") (pin "6") (pinfunction "6_6") (pintype "passive"))
      (node (ref "J2") (pin "7") (pinfunction "7_7") (pintype "passive"))
      (node (ref "R2") (pin "1") (pinfunction "1_1") (pintype "passive"))
      (node (ref "R35") (pin "1") (pinfunction "1_1") (pintype "passive"))
      (node (ref "U21") (pin "2") (pinfunction "GND_2") (pintype "power_in"))
    )
    (net (code "9") (name "Net-(12V-PadC)") (class "Default")
      (node (ref "12V") (pin "C") (pinfunction "C_C") (pintype "passive"))
      (node (ref "R2") (pin "2") (pinfunction "2_2") (pintype "passive"))
    )
    (net (code "10") (name "Net-(50V-PadTP)") (class "Default")
      (node (ref "50V") (pin "TP") (pinfunction "TP_TP") (pintype "passive"))
      (node (ref "C1") (pin "+") (pinfunction "+_+") (pintype "passive"))
      (node (ref "D22") (pin "C") (pinfunction "C_C") (pintype "passive"))
      (node (ref "R32") (pin "2") (pinfunction "2_2") (pintype "passive"))
    )
    (net (code "11") (name "Net-(F1-1)") (class "Default")
      (node (ref "F1") (pin "P$1") (pinfunction "1_P$1") (pintype "passive"))
      (node (ref "J1") (pin "3") (pinfunction "3_3") (pintype "passive"))
      (node (ref "J1") (pin "4") (pinfunction "4_4") (pintype "passive"))
      (node (ref "J1") (pin "5") (pinfunction "5_5") (pintype "passive"))
      (node (ref "J2") (pin "3") (pinfunction "3_3") (pintype "passive"))
      (node (ref "J2") (pin "4") (pinfunction "4_4") (pintype "passive"))
      (node (ref "J2") (pin "5") (pinfunction "5_5") (pintype "passive"))
    )
    (net (code "12") (name "Net-(F1-2)") (class "Default")
      (node (ref "D18") (pin "A") (pinfunction "A_A") (pintype "passive"))
      (node (ref "F1") (pin "P$2") (pinfunction "2_P$2") (pintype "passive"))
    )
    (net (code "13") (name "Net-(FAULT-PadC)") (class "Default")
      (node (ref "FAULT") (pin "C") (pinfunction "C_C") (pintype "passive"))
      (node (ref "R85") (pin "2") (pinfunction "2_2") (pintype "passive"))
    )
    (net (code "14") (name "Net-(IC8A-A)") (class "Default")
      (node (ref "IC8") (pin "10") (pinfunction "A_10") (pintype "passive"))
      (node (ref "R65") (pin "1") (pinfunction "1_1") (pintype "passive"))
      (node (ref "U1") (pin "33") (pinfunction "GPIO5_33") (pintype "passive"))
    )
    (net (code "15") (name "Net-(IC8A-B)") (class "Default")
      (node (ref "IC8") (pin "9") (pinfunction "B_9") (pintype "passive"))
      (node (ref "R64") (pin "1") (pinfunction "1_1") (pintype "passive"))
      (node (ref "U1") (pin "32") (pinfunction "GPIO4_32") (pintype "passive"))
    )
    (net (code "16") (name "Net-(IC8A-X)") (class "Default")
      (node (ref "IC8") (pin "13") (pinfunction "X_13") (pintype "passive"))
      (node (ref "U147") (pin "12") (pinfunction "+IN_12") (pintype "passive"))
    )
    (net (code "17") (name "Net-(IC8A-X0)") (class "Default")
      (node (ref "IC8") (pin "12") (pinfunction "X0_12") (pintype "passive"))
      (node (ref "R74") (pin "1") (pinfunction "1_1") (pintype "passive"))
      (node (ref "X3") (pin "1") (pinfunction "1_1") (pintype "passive"))
    )
    (net (code "18") (name "Net-(IC8A-X1)") (class "Default")
      (node (ref "IC8") (pin "14") (pinfunction "X1_14") (pintype "passive"))
      (node (ref "R73") (pin "1") (pinfunction "1_1") (pintype "passive"))
      (node (ref "X3") (pin "3") (pinfunction "3_3") (pintype "passive"))
    )
    (net (code "19") (name "Net-(IC8A-X2)") (class "Default")
      (node (ref "IC8") (pin "15") (pinfunction "X2_15") (pintype "passive"))
      (node (ref "R72") (pin "1") (pinfunction "1_1") (pintype "passive"))
      (node (ref "X3") (pin "5") (pinfunction "5_5") (pintype "passive"))
    )
    (net (code "20") (name "Net-(IC8A-X3)") (class "Default")
      (node (ref "IC8") (pin "11") (pinfunction "X3_11") (pintype "passive"))
      (node (ref "R71") (pin "1") (pinfunction "1_1") (pintype "passive"))
      (node (ref "X3") (pin "7") (pinfunction "7_7") (pintype "passive"))
    )
    (net (code "21") (name "Net-(IC8A-Y)") (class "Default")
      (node (ref "IC8") (pin "3") (pinfunction "Y_3") (pintype "passive"))
      (node (ref "U147") (pin "5") (pinfunction "+IN_5") (pintype "passive"))
    )
    (net (code "22") (name "Net-(IC8A-Y0)") (class "Default")
      (node (ref "IC8") (pin "1") (pinfunction "Y0_1") (pintype "passive"))
      (node (ref "R70") (pin "1") (pinfunction "1_1") (pintype "passive"))
      (node (ref "X3") (pin "9") (pinfunction "9_9") (pintype "passive"))
    )
    (net (code "23") (name "Net-(IC8A-Y1)") (class "Default")
      (node (ref "IC8") (pin "5") (pinfunction "Y1_5") (pintype "passive"))
      (node (ref "R69") (pin "1") (pinfunction "1_1") (pintype "passive"))
      (node (ref "X3") (pin "11") (pinfunction "11_11") (pintype "passive"))
    )
    (net (code "24") (name "Net-(IC8A-Y2)") (class "Default")
      (node (ref "IC8") (pin "2") (pinfunction "Y2_2") (pintype "passive"))
      (node (ref "R68") (pin "1") (pinfunction "1_1") (pintype "passive"))
      (node (ref "X3") (pin "13") (pinfunction "13_13") (pintype "passive"))
    )
    (net (code "25") (name "Net-(IC8A-Y3)") (class "Default")
      (node (ref "IC8") (pin "4") (pinfunction "Y3_4") (pintype "passive"))
      (node (ref "R67") (pin "1") (pinfunction "1_1") (pintype "passive"))
      (node (ref "X3") (pin "15") (pinfunction "15_15") (pintype "passive"))
    )
    (net (code "26") (name "Net-(Q3-D)") (class "Default")
      (node (ref "Q3") (pin "3") (pinfunction "D_3") (pintype "passive"))
      (node (ref "R6") (pin "2") (pinfunction "2_2") (pintype "passive"))
    )
    (net (code "27") (name "Net-(Q3-G)") (class "Default")
      (node (ref "Q3") (pin "1") (pinfunction "G_1") (pintype "passive"))
      (node (ref "R36") (pin "1") (pinfunction "1_1") (pintype "passive"))
    )
    (net (code "28") (name "Net-(Q3-S)") (class "Default")
      (node (ref "Q3") (pin "2") (pinfunction "S_2") (pintype "passive"))
      (node (ref "R1") (pin "1") (pinfunction "1_1") (pintype "passive"))
      (node (ref "X2") (pin "2") (pinfunction "2_2") (pintype "passive"))
    )
    (net (code "29") (name "Net-(Q4-D)") (class "Default")
      (node (ref "Q4") (pin "3") (pinfunction "D_3") (pintype "passive"))
      (node (ref "R8") (pin "2") (pinfunction "2_2") (pintype "passive"))
    )
    (net (code "30") (name "Net-(Q4-G)") (class "Default")
      (node (ref "Q4") (pin "1") (pinfunction "G_1") (pintype "passive"))
      (node (ref "R37") (pin "1") (pinfunction "1_1") (pintype "passive"))
    )
    (net (code "31") (name "Net-(Q4-S)") (class "Default")
      (node (ref "Q4") (pin "2") (pinfunction "S_2") (pintype "passive"))
      (node (ref "R6") (pin "1") (pinfunction "1_1") (pintype "passive"))
      (node (ref "R7") (pin "1") (pinfunction "1_1") (pintype "passive"))
      (node (ref "X2") (pin "4") (pinfunction "4_4") (pintype "passive"))
    )
    (net (code "32") (name "Net-(Q5-D)") (class "Default")
      (node (ref "Q5") (pin "3") (pinfunction "D_3") (pintype "passive"))
      (node (ref "R10") (pin "2") (pinfunction "2_2") (pintype "passive"))
    )
    (net (code "33") (name "Net-(Q5-G)") (class "Default")
      (node (ref "Q5") (pin "1") (pinfunction "G_1") (pintype "passive"))
      (node (ref "R38") (pin "1") (pinfunction "1_1") (pintype "passive"))
    )
    (net (code "34") (name "Net-(Q5-S)") (class "Default")
      (node (ref "Q5") (pin "2") (pinfunction "S_2") (pintype "passive"))
      (node (ref "R8") (pin "1") (pinfunction "1_1") (pintype "passive"))
      (node (ref "R9") (pin "1") (pinfunction "1_1") (pintype "passive"))
      (node (ref "X2") (pin "6") (pinfunction "6_6") (pintype "passive"))
    )
    (net (code "35") (name "Net-(Q6-D)") (class "Default")
      (node (ref "Q6") (pin "3") (pinfunction "D_3") (pintype "passive"))
      (node (ref "R12") (pin "2") (pinfunction "2_2") (pintype "passive"))
    )
    (net (code "36") (name "Net-(Q6-G)") (class "Default")
      (node (ref "Q6") (pin "1") (pinfunction "G_1") (pintype "passive"))
      (node (ref "R39") (pin "1") (pinfunction "1_1") (pintype "passive"))
    )
    (net (code "37") (name "Net-(Q6-S)") (class "Default")
      (node (ref "Q6") (pin "2") (pinfunction "S_2") (pintype "passive"))
      (node (ref "R10") (pin "1") (pinfunction "1_1") (pintype "passive"))
      (node (ref "R11") (pin "1") (pinfunction "1_1") (pintype "passive"))
      (node (ref "X2") (pin "8") (pinfunction "8_8") (pintype "passive"))
    )
    (net (code "38") (name "Net-(Q7-D)") (class "Default")
      (node (ref "Q7") (pin "3") (pinfunction "D_3") (pintype "passive"))
      (node (ref "R14") (pin "2") (pinfunction "2_2") (pintype "passive"))
    )
    (net (code "39") (name "Net-(Q7-G)") (class "Default")
      (node (ref "Q7") (pin "1") (pinfunction "G_1") (pintype "passive"))
      (node (ref "R40") (pin "1") (pinfunction "1_1") (pintype "passive"))
    )
    (net (code "40") (name "Net-(Q7-S)") (class "Default")
      (node (ref "Q7") (pin "2") (pinfunction "S_2") (pintype "passive"))
      (node (ref "R12") (pin "1") (pinfunction "1_1") (pintype "passive"))
      (node (ref "R13") (pin "1") (pinfunction "1_1") (pintype "passive"))
      (node (ref "X2") (pin "10") (pinfunction "10_10") (pintype "passive"))
    )
    (net (code "41") (name "Net-(Q8-D)") (class "Default")
      (node (ref "Q8") (pin "3") (pinfunction "D_3") (pintype "passive"))
      (node (ref "R16") (pin "2") (pinfunction "2_2") (pintype "passive"))
    )
    (net (code "42") (name "Net-(Q8-G)") (class "Default")
      (node (ref "Q8") (pin "1") (pinfunction "G_1") (pintype "passive"))
      (node (ref "R41") (pin "1") (pinfunction "1_1") (pintype "passive"))
    )
    (net (code "43") (name "Net-(Q8-S)") (class "Default")
      (node (ref "Q8") (pin "2") (pinfunction "S_2") (pintype "passive"))
      (node (ref "R14") (pin "1") (pinfunction "1_1") (pintype "passive"))
      (node (ref "R15") (pin "1") (pinfunction "1_1") (pintype "passive"))
      (node (ref "X2") (pin "12") (pinfunction "12_12") (pintype "passive"))
    )
    (net (code "44") (name "Net-(Q9-D)") (class "Default")
      (node (ref "Q9") (pin "3") (pinfunction "D_3") (pintype "passive"))
      (node (ref "R18") (pin "2") (pinfunction "2_2") (pintype "passive"))
    )
    (net (code "45") (name "Net-(Q9-G)") (class "Default")
      (node (ref "Q9") (pin "1") (pinfunction "G_1") (pintype "passive"))
      (node (ref "R42") (pin "1") (pinfunction "1_1") (pintype "passive"))
    )
    (net (code "46") (name "Net-(Q9-S)") (class "Default")
      (node (ref "Q9") (pin "2") (pinfunction "S_2") (pintype "passive"))
      (node (ref "R16") (pin "1") (pinfunction "1_1") (pintype "passive"))
      (node (ref "R17") (pin "1") (pinfunction "1_1") (pintype "passive"))
      (node (ref "X2") (pin "14") (pinfunction "14_14") (pintype "passive"))
    )
    (net (code "47") (name "Net-(Q10-D)") (class "Default")
      (node (ref "Q10") (pin "3") (pinfunction "D_3") (pintype "passive"))
      (node (ref "R20") (pin "2") (pinfunction "2_2") (pintype "passive"))
    )
    (net (code "48") (name "Net-(Q10-G)") (class "Default")
      (node (ref "Q10") (pin "1") (pinfunction "G_1") (pintype "passive"))
      (node (ref "R43") (pin "1") (pinfunction "1_1") (pintype "passive"))
    )
    (net (code "49") (name "Net-(Q10-S)") (class "Default")
      (node (ref "Q10") (pin "2") (pinfunction "S_2") (pintype "passive"))
      (node (ref "R18") (pin "1") (pinfunction "1_1") (pintype "passive"))
      (node (ref "R19") (pin "1") (pinfunction "1_1") (pintype "passive"))
      (node (ref "X2") (pin "16") (pinfunction "16_16") (pintype "passive"))
    )
    (net (code "50") (name "Net-(Q11-D)") (class "Default")
      (node (ref "Q11") (pin "3") (pinfunction "D_3") (pintype "passive"))
      (node (ref "R22") (pin "2") (pinfunction "2_2") (pintype "passive"))
    )
    (net (code "51") (name "Net-(Q11-G)") (class "Default")
      (node (ref "Q11") (pin "1") (pinfunction "G_1") (pintype "passive"))
      (node (ref "R44") (pin "1") (pinfunction "1_1") (pintype "passive"))
    )
    (net (code "52") (name "Net-(Q11-S)") (class "Default")
      (node (ref "Q11") (pin "2") (pinfunction "S_2") (pintype "passive"))
      (node (ref "R20") (pin "1") (pinfunction "1_1") (pintype "passive"))
      (node (ref "R21") (pin "1") (pinfunction "1_1") (pintype "passive"))
      (node (ref "X2") (pin "1") (pinfunction "1_1") (pintype "passive"))
    )
    (net (code "53") (name "Net-(Q12-G)") (class "Default")
      (node (ref "Q12") (pin "1") (pinfunction "G_1") (pintype "passive"))
      (node (ref "R45") (pin "1") (pinfunction "1_1") (pintype "passive"))
    )
    (net (code "54") (name "Net-(Q12-S)") (class "Default")
      (node (ref "Q12") (pin "2") (pinfunction "S_2") (pintype "passive"))
      (node (ref "R22") (pin "1") (pinfunction "1_1") (pintype "passive"))
      (node (ref "R23") (pin "1") (pinfunction "1_1") (pintype "passive"))
      (node (ref "X2") (pin "3") (pinfunction "3_3") (pintype "passive"))
    )
    (net (code "55") (name "Net-(Q13-D)") (class "Default")
      (node (ref "Q13") (pin "3") (pinfunction "D_3") (pintype "passive"))
      (node (ref "R26") (pin "2") (pinfunction "2_2") (pintype "passive"))
    )
    (net (code "56") (name "Net-(Q13-G)") (class "Default")
      (node (ref "Q13") (pin "1") (pinfunction "G_1") (pintype "passive"))
      (node (ref "R46") (pin "1") (pinfunction "1_1") (pintype "passive"))
    )
    (net (code "57") (name "Net-(Q13-S)") (class "Default")
      (node (ref "Q13") (pin "2") (pinfunction "S_2") (pintype "passive"))
      (node (ref "R24") (pin "1") (pinfunction "1_1") (pintype "passive"))
      (node (ref "R25") (pin "1") (pinfunction "1_1") (pintype "passive"))
      (node (ref "X2") (pin "5") (pinfunction "5_5") (pintype "passive"))
    )
    (net (code "58") (name "Net-(Q14-D)") (class "Default")
      (node (ref "Q14") (pin "3") (pinfunction "D_3") (pintype "passive"))
      (node (ref "R28") (pin "2") (pinfunction "2_2") (pintype "passive"))
    )
    (net (code "59") (name "Net-(Q14-G)") (class "Default")
      (node (ref "Q14") (pin "1") (pinfunction "G_1") (pintype "passive"))
      (node (ref "R47") (pin "1") (pinfunction "1_1") (pintype "passive"))
    )
    (net (code "60") (name "Net-(Q14-S)") (class "Default")
      (node (ref "Q14") (pin "2") (pinfunction "S_2") (pintype "passive"))
      (node (ref "R26") (pin "1") (pinfunction "1_1") (pintype "passive"))
      (node (ref "R27") (pin "1") (pinfunction "1_1") (pintype "passive"))
      (node (ref "X2") (pin "7") (pinfunction "7_7") (pintype "passive"))
    )
    (net (code "61") (name "Net-(Q21-B)") (class "Default")
      (node (ref "Q21") (pin "1") (pinfunction "B_1") (pintype "passive"))
      (node (ref "U1") (pin "38") (pinfunction "DRIVE_38") (pintype "passive"))
    )
    (net (code "62") (name "Net-(Q21-C2)") (class "Default")
      (node (ref "C2") (pin "1") (pinfunction "1_1") (pintype "passive"))
      (node (ref "Q21") (pin "2") (pinfunction "C2_2") (pintype "passive"))
      (node (ref "Q21") (pin "4") (pinfunction "C4_4") (pintype "passive"))
      (node (ref "Z2") (pin "C") (pinfunction "C_C") (pintype "passive"))
    )
    (net (code "63") (name "Net-(U$3-P1)") (class "Default")
      (node (ref "J1") (pin "2") (pinfunction "2_2") (pintype "passive"))
      (node (ref "J2") (pin "2") (pinfunction "2_2") (pintype "passive"))
      (node (ref "TP4") (pin "TP") (pinfunction "TP_TP") (pintype "passive"))
      (node (ref "U$3") (pin "P$1") (pinfunction "P1_P$1") (pintype "passive"))
    )
    (net (code "64") (name "Net-(U$3-P3)") (class "Default")
      (node (ref "J1") (pin "1") (pinfunction "1_1") (pintype "passive"))
      (node (ref "J2") (pin "1") (pinfunction "1_1") (pintype "passive"))
      (node (ref "TP3") (pin "TP") (pinfunction "TP_TP") (pintype "passive"))
      (node (ref "U$3") (pin "P$3") (pinfunction "P3_P$3") (pintype "passive"))
    )
    (net (code "65") (name "Net-(U$3-S4)") (class "Default")
      (node (ref "TP1") (pin "TP") (pinfunction "TP_TP") (pintype "passive"))
      (node (ref "U$1") (pin "P$2") (pinfunction "P$2_P$2") (pintype "passive"))
      (node (ref "U$3") (pin "P$4") (pinfunction "S4_P$4") (pintype "passive"))
    )
    (net (code "66") (name "Net-(U$3-S5)") (class "Default")
      (node (ref "C43") (pin "1") (pinfunction "1_1") (pintype "passive"))
      (node (ref "U$3") (pin "P$5") (pinfunction "S5_P$5") (pintype "passive"))
    )
    (net (code "67") (name "Net-(U$3-S6)") (class "Default")
      (node (ref "TP2") (pin "TP") (pinfunction "TP_TP") (pintype "passive"))
      (node (ref "U$1") (pin "P$3") (pinfunction "P$3_P$3") (pintype "passive"))
      (node (ref "U$3") (pin "P$6") (pinfunction "S6_P$6") (pintype "passive"))
    )
    (net (code "68") (name "Net-(U$15-PRI_2)") (class "Default")
      (node (ref "U$15") (pin "P$2") (pinfunction "PRI_2_P$2") (pintype "passive"))
      (node (ref "U$15") (pin "P$4") (pinfunction "PRI_4_P$4") (pintype "passive"))
      (node (ref "Z2") (pin "A") (pinfunction "A_A") (pintype "passive"))
    )
    (net (code "69") (name "Net-(U$15-PRI_3)") (class "Default")
      (node (ref "D22") (pin "A") (pinfunction "A_A") (pintype "passive"))
      (node (ref "U$15") (pin "P$3") (pinfunction "PRI_3_P$3") (pintype "passive"))
    )
    (net (code "70") (name "Net-(U$15-SEC5)") (class "Default")
      (node (ref "R33") (pin "1") (pinfunction "1_1") (pintype "passive"))
      (node (ref "U$15") (pin "P$5") (pinfunction "SEC5_P$5") (pintype "passive"))
      (node (ref "U$15") (pin "P$6") (pinfunction "SEC6_P$6") (pintype "passive"))
      (node (ref "U21") (pin "4") (pinfunction "SW_4") (pintype "passive"))
    )
    (net (code "71") (name "Net-(U1-A1)") (class "Default")
      (node (ref "R75") (pin "2") (pinfunction "2_2") (pintype "passive"))
      (node (ref "R80") (pin "1") (pinfunction "1_1") (pintype "passive"))
      (node (ref "U1") (pin "46") (pinfunction "A1_46") (pintype "passive"))
    )
    (net (code "72") (name "Net-(U1-A3)") (class "Default")
      (node (ref "R78") (pin "2") (pinfunction "2_2") (pintype "passive"))
      (node (ref "R82") (pin "1") (pinfunction "1_1") (pintype "passive"))
      (node (ref "U1") (pin "48") (pinfunction "A3_48") (pintype "passive"))
    )
    (net (code "73") (name "Net-(U1-C0)") (class "Default")
      (node (ref "C17") (pin "1") (pinfunction "1_1") (pintype "passive"))
      (node (ref "D12") (pin "A") (pinfunction "A_A") (pintype "passive"))
      (node (ref "D19") (pin "C") (pinfunction "C_C") (pintype "passive"))
      (node (ref "R84") (pin "2") (pinfunction "2_2") (pintype "passive"))
      (node (ref "R87") (pin "2") (pinfunction "2_2") (pintype "passive"))
      (node (ref "U1") (pin "26") (pinfunction "C0_26") (pintype "passive"))
    )
    (net (code "74") (name "Net-(U1-C1)") (class "Default")
      (node (ref "C16") (pin "1") (pinfunction "1_1") (pintype "passive"))
      (node (ref "D11") (pin "A") (pinfunction "A_A") (pintype "passive"))
      (node (ref "D12") (pin "C") (pinfunction "C_C") (pintype "passive"))
      (node (ref "R27") (pin "2") (pinfunction "2_2") (pintype "passive"))
      (node (ref "R52") (pin "2") (pinfunction "2_2") (pintype "passive"))
      (node (ref "R84") (pin "1") (pinfunction "1_1") (pintype "passive"))
      (node (ref "U1") (pin "24") (pinfunction "C1_24") (pintype "passive"))
    )
    (net (code "75") (name "Net-(U1-C2)") (class "Default")
      (node (ref "C15") (pin "1") (pinfunction "1_1") (pintype "passive"))
      (node (ref "D10") (pin "A") (pinfunction "A_A") (pintype "passive"))
      (node (ref "D11") (pin "C") (pinfunction "C_C") (pintype "passive"))
      (node (ref "R25") (pin "2") (pinfunction "2_2") (pintype "passive"))
      (node (ref "R51") (pin "2") (pinfunction "2_2") (pintype "passive"))
      (node (ref "R52") (pin "1") (pinfunction "1_1") (pintype "passive"))
      (node (ref "U1") (pin "22") (pinfunction "C2_22") (pintype "passive"))
    )
    (net (code "76") (name "Net-(U1-C3)") (class "Default")
      (node (ref "C14") (pin "1") (pinfunction "1_1") (pintype "passive"))
      (node (ref "D10") (pin "C") (pinfunction "C_C") (pintype "passive"))
      (node (ref "D9") (pin "A") (pinfunction "A_A") (pintype "passive"))
      (node (ref "R23") (pin "2") (pinfunction "2_2") (pintype "passive"))
      (node (ref "R50") (pin "2") (pinfunction "2_2") (pintype "passive"))
      (node (ref "R51") (pin "1") (pinfunction "1_1") (pintype "passive"))
      (node (ref "U1") (pin "20") (pinfunction "C3_20") (pintype "passive"))
    )
    (net (code "77") (name "Net-(U1-C4)") (class "Default")
      (node (ref "C13") (pin "1") (pinfunction "1_1") (pintype "passive"))
      (node (ref "D8") (pin "A") (pinfunction "A_A") (pintype "passive"))
      (node (ref "D9") (pin "C") (pinfunction "C_C") (pintype "passive"))
      (node (ref "R21") (pin "2") (pinfunction "2_2") (pintype "passive"))
      (node (ref "R49") (pin "2") (pinfunction "2_2") (pintype "passive"))
      (node (ref "R50") (pin "1") (pinfunction "1_1") (pintype "passive"))
      (node (ref "U1") (pin "18") (pinfunction "C4_18") (pintype "passive"))
    )
    (net (code "78") (name "Net-(U1-C5)") (class "Default")
      (node (ref "C12") (pin "1") (pinfunction "1_1") (pintype "passive"))
      (node (ref "D7") (pin "A") (pinfunction "A_A") (pintype "passive"))
      (node (ref "D8") (pin "C") (pinfunction "C_C") (pintype "passive"))
      (node (ref "R19") (pin "2") (pinfunction "2_2") (pintype "passive"))
      (node (ref "R31") (pin "2") (pinfunction "2_2") (pintype "passive"))
      (node (ref "R49") (pin "1") (pinfunction "1_1") (pintype "passive"))
      (node (ref "U1") (pin "16") (pinfunction "C5_16") (pintype "passive"))
    )
    (net (code "79") (name "Net-(U1-C6)") (class "Default")
      (node (ref "C11") (pin "1") (pinfunction "1_1") (pintype "passive"))
      (node (ref "D6") (pin "A") (pinfunction "A_A") (pintype "passive"))
      (node (ref "D7") (pin "C") (pinfunction "C_C") (pintype "passive"))
      (node (ref "R17") (pin "2") (pinfunction "2_2") (pintype "passive"))
      (node (ref "R30") (pin "2") (pinfunction "2_2") (pintype "passive"))
      (node (ref "R31") (pin "1") (pinfunction "1_1") (pintype "passive"))
      (node (ref "U1") (pin "14") (pinfunction "C6_14") (pintype "passive"))
    )
    (net (code "80") (name "Net-(U1-C7)") (class "Default")
      (node (ref "C10") (pin "1") (pinfunction "1_1") (pintype "passive"))
      (node (ref "D5") (pin "A") (pinfunction "A_A") (pintype "passive"))
      (node (ref "D6") (pin "C") (pinfunction "C_C") (pintype "passive"))
      (node (ref "R15") (pin "2") (pinfunction "2_2") (pintype "passive"))
      (node (ref "R29") (pin "2") (pinfunction "2_2") (pintype "passive"))
      (node (ref "R30") (pin "1") (pinfunction "1_1") (pintype "passive"))
      (node (ref "U1") (pin "12") (pinfunction "C7_12") (pintype "passive"))
    )
    (net (code "81") (name "Net-(U1-C8)") (class "Default")
      (node (ref "C8") (pin "1") (pinfunction "1_1") (pintype "passive"))
      (node (ref "D4") (pin "A") (pinfunction "A_A") (pintype "passive"))
      (node (ref "D5") (pin "C") (pinfunction "C_C") (pintype "passive"))
      (node (ref "R13") (pin "2") (pinfunction "2_2") (pintype "passive"))
      (node (ref "R29") (pin "1") (pinfunction "1_1") (pintype "passive"))
      (node (ref "R5") (pin "2") (pinfunction "2_2") (pintype "passive"))
      (node (ref "U1") (pin "10") (pinfunction "C8_10") (pintype "passive"))
    )
    (net (code "82") (name "Net-(U1-C9)") (class "Default")
      (node (ref "C7") (pin "1") (pinfunction "1_1") (pintype "passive"))
      (node (ref "D3") (pin "A") (pinfunction "A_A") (pintype "passive"))
      (node (ref "D4") (pin "C") (pinfunction "C_C") (pintype "passive"))
      (node (ref "R11") (pin "2") (pinfunction "2_2") (pintype "passive"))
      (node (ref "R4") (pin "2") (pinfunction "2_2") (pintype "passive"))
      (node (ref "R5") (pin "1") (pinfunction "1_1") (pintype "passive"))
      (node (ref "U1") (pin "8") (pinfunction "C9_8") (pintype "passive"))
    )
    (net (code "83") (name "Net-(U1-C10)") (class "Default")
      (node (ref "C5") (pin "1") (pinfunction "1_1") (pintype "passive"))
      (node (ref "D2") (pin "A") (pinfunction "A_A") (pintype "passive"))
      (node (ref "D3") (pin "C") (pinfunction "C_C") (pintype "passive"))
      (node (ref "R3") (pin "2") (pinfunction "2_2") (pintype "passive"))
      (node (ref "R4") (pin "1") (pinfunction "1_1") (pintype "passive"))
      (node (ref "R9") (pin "2") (pinfunction "2_2") (pintype "passive"))
      (node (ref "U1") (pin "6") (pinfunction "C10_6") (pintype "passive"))
    )
    (net (code "84") (name "Net-(U1-C11)") (class "Default")
      (node (ref "C4") (pin "1") (pinfunction "1_1") (pintype "passive"))
      (node (ref "D1") (pin "A") (pinfunction "A_A") (pintype "passive"))
      (node (ref "D2") (pin "C") (pinfunction "C_C") (pintype "passive"))
      (node (ref "R3") (pin "1") (pinfunction "1_1") (pintype "passive"))
      (node (ref "R48") (pin "2") (pinfunction "2_2") (pintype "passive"))
      (node (ref "R7") (pin "2") (pinfunction "2_2") (pintype "passive"))
      (node (ref "U1") (pin "4") (pinfunction "C11_4") (pintype "passive"))
    )
    (net (code "85") (name "Net-(U1-C12)") (class "Default")
      (node (ref "C9") (pin "1") (pinfunction "1_1") (pintype "passive"))
      (node (ref "D1") (pin "C") (pinfunction "C_C") (pintype "passive"))
      (node (ref "R1") (pin "2") (pinfunction "2_2") (pintype "passive"))
      (node (ref "R48") (pin "1") (pinfunction "1_1") (pintype "passive"))
      (node (ref "U1") (pin "2") (pinfunction "C12_2") (pintype "passive"))
    )
    (net (code "86") (name "Net-(U1-CSB(IMA)*)") (class "Default")
      (node (ref "R83") (pin "1") (pinfunction "1_1") (pintype "passive"))
      (node (ref "U$1") (pin "P$4") (pinfunction "P$4_P$4") (pintype "passive"))
      (node (ref "U1") (pin "41") (pinfunction "CSB(IMA)*_41") (pintype "passive"))
    )
    (net (code "87") (name "Net-(U1-GPIO1)") (class "Default")
      (node (ref "C19") (pin "1") (pinfunction "1_1") (pintype "passive"))
      (node (ref "R54") (pin "1") (pinfunction "1_1") (pintype "passive"))
      (node (ref "U1") (pin "27") (pinfunction "GPIO1_27") (pintype "passive"))
    )
    (net (code "88") (name "Net-(U1-GPIO2)") (class "Default")
      (node (ref "C18") (pin "1") (pinfunction "1_1") (pintype "passive"))
      (node (ref "R53") (pin "1") (pinfunction "1_1") (pintype "passive"))
      (node (ref "U1") (pin "28") (pinfunction "GPIO2_28") (pintype "passive"))
    )
    (net (code "89") (name "Net-(U1-GPIO3)") (class "Default")
      (node (ref "FAULT") (pin "A") (pinfunction "A_A") (pintype "passive"))
      (node (ref "U1") (pin "29") (pinfunction "GPIO3_29") (pintype "passive"))
    )
    (net (code "90") (name "Net-(U1-S1)") (class "Default")
      (node (ref "R47") (pin "2") (pinfunction "2_2") (pintype "passive"))
      (node (ref "U1") (pin "25") (pinfunction "S1_25") (pintype "passive"))
    )
    (net (code "91") (name "Net-(U1-S2)") (class "Default")
      (node (ref "R46") (pin "2") (pinfunction "2_2") (pintype "passive"))
      (node (ref "U1") (pin "23") (pinfunction "S2_23") (pintype "passive"))
    )
    (net (code "92") (name "Net-(U1-S3)") (class "Default")
      (node (ref "R45") (pin "2") (pinfunction "2_2") (pintype "passive"))
      (node (ref "U1") (pin "21") (pinfunction "S3_21") (pintype "passive"))
    )
    (net (code "93") (name "Net-(U1-S4)") (class "Default")
      (node (ref "R44") (pin "2") (pinfunction "2_2") (pintype "passive"))
      (node (ref "U1") (pin "19") (pinfunction "S4_19") (pintype "passive"))
    )
    (net (code "94") (name "Net-(U1-S5)") (class "Default")
      (node (ref "R43") (pin "2") (pinfunction "2_2") (pintype "passive"))
      (node (ref "U1") (pin "17") (pinfunction "S5_17") (pintype "passive"))
    )
    (net (code "95") (name "Net-(U1-S6)") (class "Default")
      (node (ref "R42") (pin "2") (pinfunction "2_2") (pintype "passive"))
      (node (ref "U1") (pin "15") (pinfunction "S6_15") (pintype "passive"))
    )
    (net (code "96") (name "Net-(U1-S7)") (class "Default")
      (node (ref "R41") (pin "2") (pinfunction "2_2") (pintype "passive"))
      (node (ref "U1") (pin "13") (pinfunction "S7_13") (pintype "passive"))
    )
    (net (code "97") (name "Net-(U1-S8)") (class "Default")
      (node (ref "R40") (pin "2") (pinfunction "2_2") (pintype "passive"))
      (node (ref "U1") (pin "11") (pinfunction "S8_11") (pintype "passive"))
    )
    (net (code "98") (name "Net-(U1-S9)") (class "Default")
      (node (ref "R39") (pin "2") (pinfunction "2_2") (pintype "passive"))
      (node (ref "U1") (pin "9") (pinfunction "S9_9") (pintype "passive"))
    )
    (net (code "99") (name "Net-(U1-S10)") (class "Default")
      (node (ref "R38") (pin "2") (pinfunction "2_2") (pintype "passive"))
      (node (ref "U1") (pin "7") (pinfunction "S10_7") (pintype "passive"))
    )
    (net (code "100") (name "Net-(U1-S11)") (class "Default")
      (node (ref "R37") (pin "2") (pinfunction "2_2") (pintype "passive"))
      (node (ref "U1") (pin "5") (pinfunction "S11_5") (pintype "passive"))
    )
    (net (code "101") (name "Net-(U1-S12)") (class "Default")
      (node (ref "R36") (pin "2") (pinfunction "2_2") (pintype "passive"))
      (node (ref "U1") (pin "3") (pinfunction "S12_3") (pintype "passive"))
    )
    (net (code "102") (name "Net-(U1-SCK(IPA)*)") (class "Default")
      (node (ref "R83") (pin "2") (pinfunction "2_2") (pintype "passive"))
      (node (ref "U$1") (pin "P$1") (pinfunction "P$1_P$1") (pintype "passive"))
      (node (ref "U1") (pin "42") (pinfunction "SCK(IPA)*_42") (pintype "passive"))
    )
    (net (code "103") (name "Net-(U1-SDI(ICMP)*)") (class "Default")
      (node (ref "R61") (pin "1") (pinfunction "1_1") (pintype "passive"))
      (node (ref "R62") (pin "2") (pinfunction "2_2") (pintype "passive"))
      (node (ref "U1") (pin "43") (pinfunction "SDI(ICMP)*_43") (pintype "passive"))
    )
    (net (code "104") (name "Net-(U1-SDO(IBIAS)*)") (class "Default")
      (node (ref "R62") (pin "1") (pinfunction "1_1") (pintype "passive"))
      (node (ref "U1") (pin "44") (pinfunction "SDO(IBIAS)*_44") (pintype "passive"))
    )
    (net (code "105") (name "Net-(U1-SWTEN)") (class "Default")
      (node (ref "R63") (pin "1") (pinfunction "1_1") (pintype "passive"))
      (node (ref "U1") (pin "36") (pinfunction "SWTEN_36") (pintype "passive"))
    )
    (net (code "106") (name "Net-(U1-WDT)") (class "Default")
      (node (ref "R66") (pin "1") (pinfunction "1_1") (pintype "passive"))
      (node (ref "U1") (pin "39") (pinfunction "WDT_39") (pintype "passive"))
    )
    (net (code "107") (name "Net-(U21-EN{slash}UVLO)") (class "Default")
      (node (ref "R34") (pin "1") (pinfunction "1_1") (pintype "passive"))
      (node (ref "R35") (pin "2") (pinfunction "2_2") (pintype "passive"))
      (node (ref "U21") (pin "1") (pinfunction "EN/UVLO_1") (pintype "passive"))
    )
    (net (code "108") (name "Net-(U21-RFB)") (class "Default")
      (node (ref "R33") (pin "2") (pinfunction "2_2") (pintype "passive"))
      (node (ref "U21") (pin "3") (pinfunction "RFB_3") (pintype "passive"))
    )
    (net (code "109") (name "Net-(U147A--IN)") (class "Default")
      (node (ref "R55") (pin "2") (pinfunction "2_2") (pintype "passive"))
      (node (ref "R56") (pin "2") (pinfunction "2_2") (pintype "passive"))
      (node (ref "U147") (pin "2") (pinfunction "-IN_2") (pintype "passive"))
    )
    (net (code "110") (name "Net-(U147A-OUT)") (class "Default")
      (node (ref "R56") (pin "1") (pinfunction "1_1") (pintype "passive"))
      (node (ref "R67") (pin "2") (pinfunction "2_2") (pintype "passive"))
      (node (ref "R68") (pin "2") (pinfunction "2_2") (pintype "passive"))
      (node (ref "R69") (pin "2") (pinfunction "2_2") (pintype "passive"))
      (node (ref "R70") (pin "2") (pinfunction "2_2") (pintype "passive"))
      (node (ref "R71") (pin "2") (pinfunction "2_2") (pintype "passive"))
      (node (ref "R72") (pin "2") (pinfunction "2_2") (pintype "passive"))
      (node (ref "R73") (pin "2") (pinfunction "2_2") (pintype "passive"))
      (node (ref "R74") (pin "2") (pinfunction "2_2") (pintype "passive"))
      (node (ref "TP7") (pin "TP") (pinfunction "TP_TP") (pintype "passive"))
      (node (ref "U147") (pin "1") (pinfunction "OUT_1") (pintype "output"))
    )
    (net (code "111") (name "Net-(U147B--IN)") (class "Default")
      (node (ref "R58") (pin "2") (pinfunction "2_2") (pintype "passive"))
      (node (ref "R60") (pin "2") (pinfunction "2_2") (pintype "passive"))
      (node (ref "U147") (pin "6") (pinfunction "-IN_6") (pintype "passive"))
    )
    (net (code "112") (name "Net-(U147B-OUT)") (class "Default")
      (node (ref "R53") (pin "2") (pinfunction "2_2") (pintype "passive"))
      (node (ref "R58") (pin "1") (pinfunction "1_1") (pintype "passive"))
      (node (ref "TP5") (pin "TP") (pinfunction "TP_TP") (pintype "passive"))
      (node (ref "U147") (pin "7") (pinfunction "OUT_7") (pintype "output"))
    )
    (net (code "113") (name "Net-(U147C--IN)") (class "Default")
      (node (ref "R57") (pin "2") (pinfunction "2_2") (pintype "passive"))
      (node (ref "R59") (pin "2") (pinfunction "2_2") (pintype "passive"))
      (node (ref "U147") (pin "11") (pinfunction "-IN_11") (pintype "passive"))
    )
    (net (code "114") (name "Net-(U147C-OUT)") (class "Default")
      (node (ref "R54") (pin "2") (pinfunction "2_2") (pintype "passive"))
      (node (ref "R57") (pin "1") (pinfunction "1_1") (pintype "passive"))
      (node (ref "TP6") (pin "TP") (pinfunction "TP_TP") (pintype "passive"))
      (node (ref "U147") (pin "10") (pinfunction "OUT_10") (pintype "output"))
    )
    (net (code "115") (name "Net-(U147D--IN)") (class "Default")
      (node (ref "U147") (pin "15") (pinfunction "-IN_15") (pintype "passive"))
      (node (ref "U147") (pin "16") (pinfunction "OUT_16") (pintype "output"))
    )
    (net (code "116") (name "V+") (class "Default")
      (node (ref "C41") (pin "1") (pinfunction "1_1") (pintype "passive"))
      (node (ref "R32") (pin "1") (pinfunction "1_1") (pintype "passive"))
      (node (ref "U1") (pin "1") (pinfunction "V+_1") (pintype "power_in"))
      (node (ref "Z1") (pin "C") (pinfunction "C_C") (pintype "passive"))
    )
    (net (code "117") (name "V-") (class "Default")
      (node (ref "C1") (pin "-") (pinfunction "-_-") (pintype "passive"))
      (node (ref "C10") (pin "2") (pinfunction "2_2") (pintype "passive"))
      (node (ref "C11") (pin "2") (pinfunction "2_2") (pintype "passive"))
      (node (ref "C12") (pin "2") (pinfunction "2_2") (pintype "passive"))
      (node (ref "C13") (pin "2") (pinfunction "2_2") (pintype "passive"))
      (node (ref "C14") (pin "2") (pinfunction "2_2") (pintype "passive"))
      (node (ref "C15") (pin "2") (pinfunction "2_2") (pintype "passive"))
      (node (ref "C16") (pin "2") (pinfunction "2_2") (pintype "passive"))
      (node (ref "C17") (pin "2") (pinfunction "2_2") (pintype "passive"))
      (node (ref "C18") (pin "2") (pinfunction "2_2") (pintype "passive"))
      (node (ref "C19") (pin "2") (pinfunction "2_2") (pintype "passive"))
      (node (ref "C2") (pin "2") (pinfunction "2_2") (pintype "passive"))
      (node (ref "C22") (pin "2") (pinfunction "2_2") (pintype "passive"))
      (node (ref "C23") (pin "2") (pinfunction "2_2") (pintype "passive"))
      (node (ref "C4") (pin "2") (pinfunction "2_2") (pintype "passive"))
      (node (ref "C41") (pin "2") (pinfunction "2_2") (pintype "passive"))
      (node (ref "C42") (pin "2") (pinfunction "2_2") (pintype "passive"))
      (node (ref "C43") (pin "2") (pinfunction "2_2") (pintype "passive"))
      (node (ref "C5") (pin "2") (pinfunction "2_2") (pintype "passive"))
      (node (ref "C50") (pin "2") (pinfunction "2_2") (pintype "passive"))
      (node (ref "C6") (pin "2") (pinfunction "2_2") (pintype "passive"))
      (node (ref "C7") (pin "2") (pinfunction "2_2") (pintype "passive"))
      (node (ref "C8") (pin "2") (pinfunction "2_2") (pintype "passive"))
      (node (ref "C9") (pin "2") (pinfunction "2_2") (pintype "passive"))
      (node (ref "D19") (pin "A") (pinfunction "A_A") (pintype "passive"))
      (node (ref "IC8") (pin "6") (pinfunction "INH_6") (pintype "passive"))
      (node (ref "IC8") (pin "7") (pinfunction "VEE_7") (pintype "power_in"))
      (node (ref "IC8") (pin "8") (pinfunction "GND_8") (pintype "power_in"))
      (node (ref "R28") (pin "1") (pinfunction "1_1") (pintype "passive"))
      (node (ref "R55") (pin "1") (pinfunction "1_1") (pintype "passive"))
      (node (ref "R59") (pin "1") (pinfunction "1_1") (pintype "passive"))
      (node (ref "R60") (pin "1") (pinfunction "1_1") (pintype "passive"))
      (node (ref "R61") (pin "2") (pinfunction "2_2") (pintype "passive"))
      (node (ref "R79") (pin "2") (pinfunction "2_2") (pintype "passive"))
      (node (ref "R80") (pin "2") (pinfunction "2_2") (pintype "passive"))
      (node (ref "R81") (pin "2") (pinfunction "2_2") (pintype "passive"))
      (node (ref "R82") (pin "2") (pinfunction "2_2") (pintype "passive"))
      (node (ref "R85") (pin "1") (pinfunction "1_1") (pintype "passive"))
      (node (ref "R87") (pin "1") (pinfunction "1_1") (pintype "passive"))
      (node (ref "U$15") (pin "P$1") (pinfunction "PRI_1_P$1") (pintype "passive"))
      (node (ref "U1") (pin "30") (pinfunction "V-**_30") (pintype "passive"))
      (node (ref "U1") (pin "31") (pinfunction "V-_31") (pintype "power_in"))
      (node (ref "U147") (pin "13") (pinfunction "V-_13") (pintype "power_in"))
      (node (ref "U147") (pin "14") (pinfunction "+IN_14") (pintype "passive"))
      (node (ref "V-") (pin "TP") (pinfunction "TP_TP") (pintype "passive"))
      (node (ref "X2") (pin "13") (pinfunction "13_13") (pintype "passive"))
      (node (ref "X3") (pin "17") (pinfunction "17_17") (pintype "passive"))
      (node (ref "X3") (pin "18") (pinfunction "18_18") (pintype "passive"))
      (node (ref "X3") (pin "19") (pinfunction "19_19") (pintype "passive"))
      (node (ref "X3") (pin "2") (pinfunction "2_2") (pintype "passive"))
      (node (ref "X3") (pin "20") (pinfunction "20_20") (pintype "passive"))
      (node (ref "X3") (pin "4") (pinfunction "4_4") (pintype "passive"))
      (node (ref "X3") (pin "6") (pinfunction "6_6") (pintype "passive"))
      (node (ref "X3") (pin "8") (pinfunction "8_8") (pintype "passive"))
      (node (ref "Z1") (pin "A") (pinfunction "A_A") (pintype "passive"))
    )
    (net (code "118") (name "unconnected-(U$3-P2-PadP$2)") (class "Default")
      (node (ref "U$3") (pin "P$2") (pinfunction "P2_P$2") (pintype "passive"))
    )
    (net (code "119") (name "unconnected-(X2-Pad9)") (class "Default")
      (node (ref "X2") (pin "9") (pinfunction "9_9") (pintype "passive"))
    )
    (net (code "120") (name "unconnected-(X2-Pad11)") (class "Default")
      (node (ref "X2") (pin "11") (pinfunction "11_11") (pintype "passive"))
    )
    (net (code "121") (name "unconnected-(X2-Pad15)") (class "Default")
      (node (ref "X2") (pin "15") (pinfunction "15_15") (pintype "passive"))
    )
    (net (code "122") (name "unconnected-(X3-Pad10)") (class "Default")
      (node (ref "X3") (pin "10") (pinfunction "10_10") (pintype "passive+no_connect"))
    )
    (net (code "123") (name "unconnected-(X3-Pad12)") (class "Default")
      (node (ref "X3") (pin "12") (pinfunction "12_12") (pintype "passive+no_connect"))
    )
    (net (code "124") (name "unconnected-(X3-Pad14)") (class "Default")
      (node (ref "X3") (pin "14") (pinfunction "14_14") (pintype "passive+no_connect"))
    )
    (net (code "125") (name "unconnected-(X3-Pad16)") (class "Default")
      (node (ref "X3") (pin "16") (pinfunction "16_16") (pintype "passive+no_connect"))
    )
  )
)
